# Sheet_1_2024-11-25.net
KiCad netlist of a schematic drawn in Altium Designer
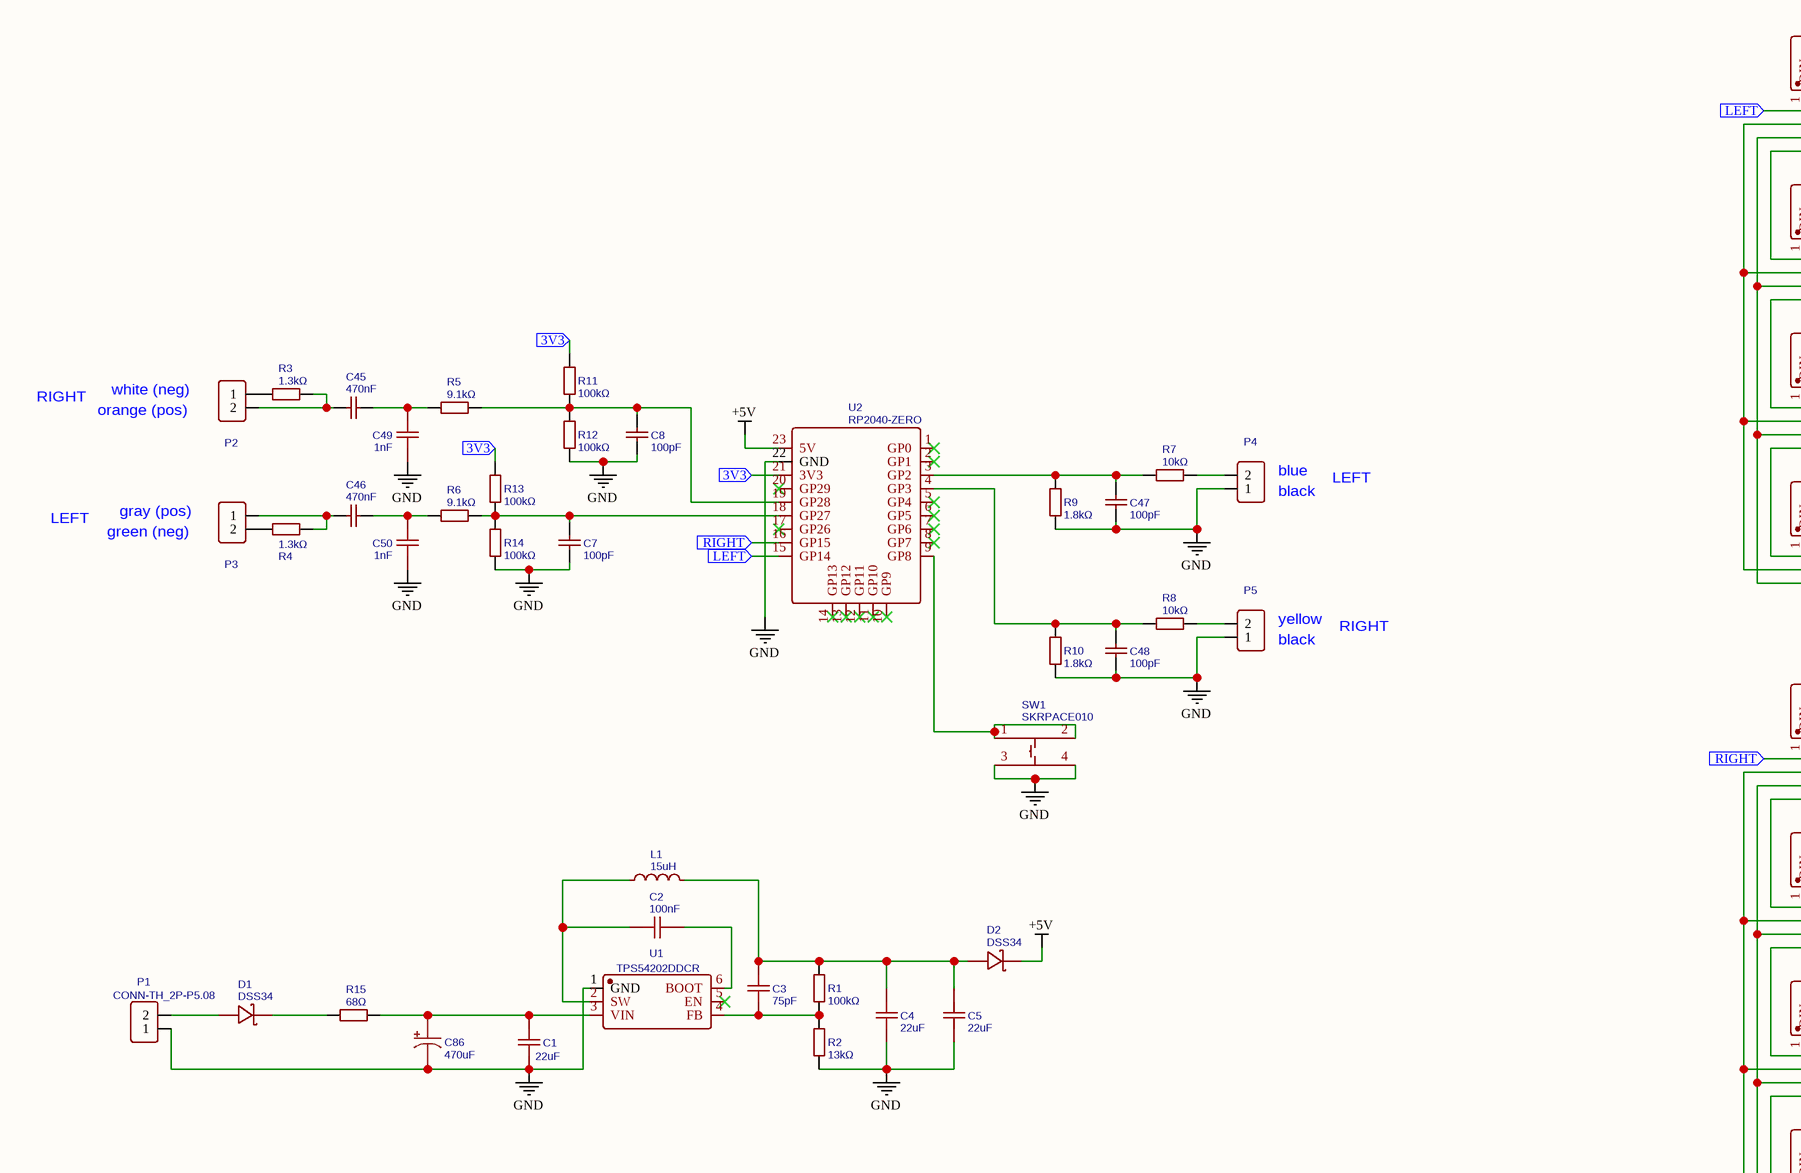
[diagram p0: Sheet_1_2024-11-25.schdoc, left]
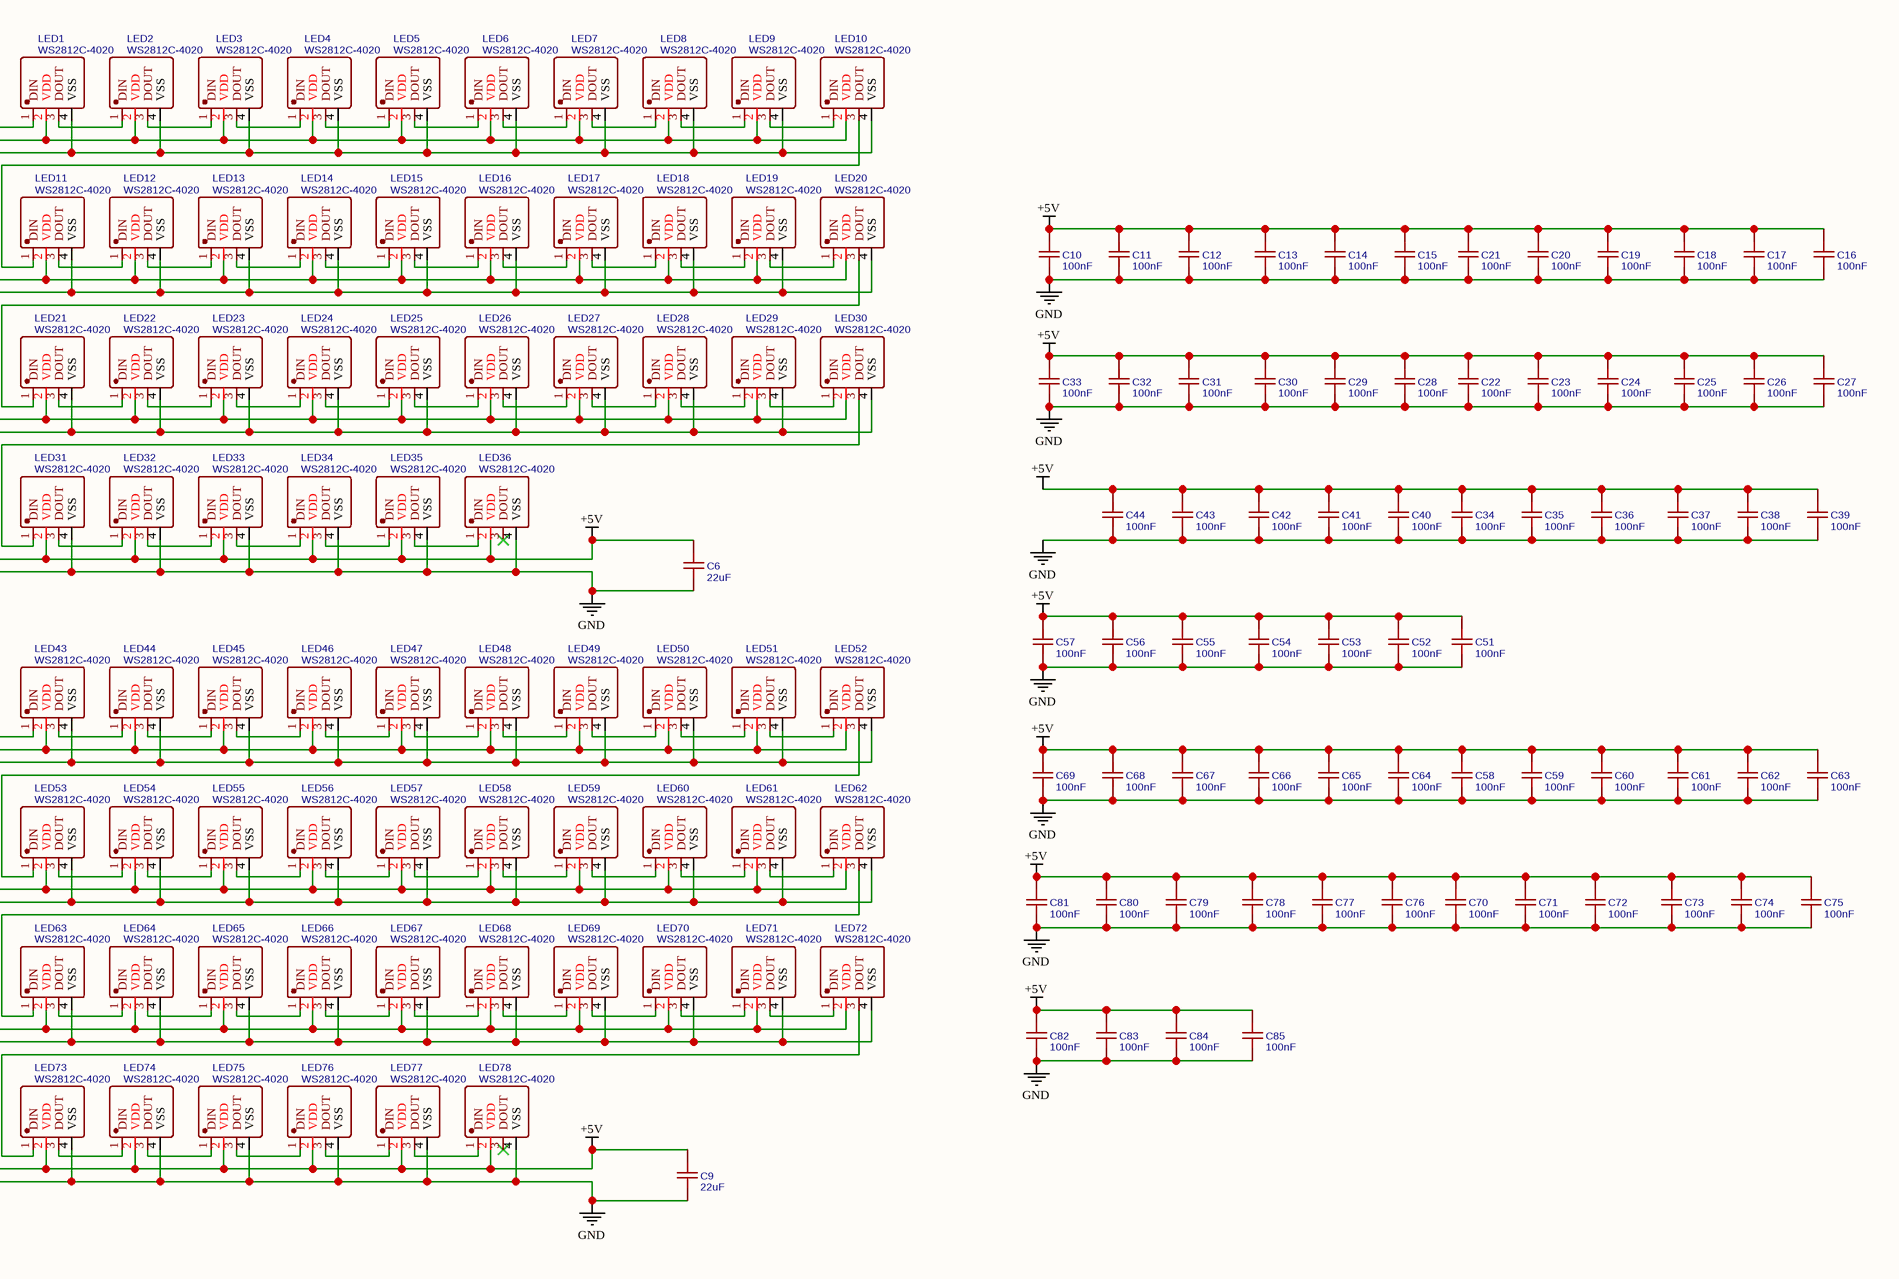
[diagram p1: Sheet_1_2024-11-25.schdoc, right]

(export (version "E")
  (design (tool "Eeschema 10.0.6"))
  (components
    (comp (ref "C1")
      (value "22uF")
      (fields
        (field (name "MANUFACTURER") "Samsung Electro-Mechanics")
        (field (name "MANUFACTURER PART") "CL21A226MAYNNNE")
        (field (name "CONTRIBUTOR") "LCSC")
      )
      (libsource (lib "altium-import") (part "root_1_22uF_"))
    )
    (comp (ref "C2")
      (value "100nF")
      (fields
        (field (name "MANUFACTURER PART") "CL05B104KO5NNNC")
        (field (name "MANUFACTURER") "SAMSUNG(三星)")
      )
      (libsource (lib "altium-import") (part "root_2_100nF_"))
    )
    (comp (ref "C3")
      (value "75pF")
      (fields
        (field (name "MANUFACTURER") "YAGEO(国巨)")
        (field (name "MANUFACTURER PART") "CC0603JRNPO9BN750")
        (field (name "CONTRIBUTOR") "LCSC")
      )
      (libsource (lib "altium-import") (part "root_0_75pF_"))
    )
    (comp (ref "C4")
      (value "22uF")
      (fields (field (name "MANUFACTURER") "SAMSUNG") (field (name "MANUFACTURER PART") "CL10A226MQ8NRNC"))
      (libsource (lib "altium-import") (part "root_1_22uF_"))
    )
    (comp (ref "C5")
      (value "22uF")
      (fields (field (name "MANUFACTURER") "SAMSUNG") (field (name "MANUFACTURER PART") "CL10A226MQ8NRNC"))
      (libsource (lib "altium-import") (part "root_1_22uF_"))
    )
    (comp (ref "C6")
      (value "22uF")
      (fields (field (name "MANUFACTURER") "SAMSUNG") (field (name "MANUFACTURER PART") "CL10A226MQ8NRNC"))
      (libsource (lib "altium-import") (part "root_1_22uF_"))
    )
    (comp (ref "C7")
      (value "100pF")
      (fields
        (field (name "MANUFACTURER PART") "CL10C101JB8NNNC")
        (field (name "MANUFACTURER") "SAMSUNG(三星)")
      )
      (libsource (lib "altium-import") (part "root_1_100pF_"))
    )
    (comp (ref "C8")
      (value "100pF")
      (fields
        (field (name "MANUFACTURER PART") "CL10C101JB8NNNC")
        (field (name "MANUFACTURER") "SAMSUNG(三星)")
      )
      (libsource (lib "altium-import") (part "root_1_100pF_"))
    )
    (comp (ref "C9")
      (value "22uF")
      (fields (field (name "MANUFACTURER") "SAMSUNG") (field (name "MANUFACTURER PART") "CL10A226MQ8NRNC"))
      (libsource (lib "altium-import") (part "root_1_22uF_"))
    )
    (comp (ref "C10")
      (value "100nF")
      (fields
        (field (name "MANUFACTURER PART") "CL05B104KO5NNNC")
        (field (name "MANUFACTURER") "SAMSUNG(三星)")
      )
      (libsource (lib "altium-import") (part "root_1_100nF_"))
    )
    (comp (ref "C11")
      (value "100nF")
      (fields
        (field (name "MANUFACTURER PART") "CL05B104KO5NNNC")
        (field (name "MANUFACTURER") "SAMSUNG(三星)")
      )
      (libsource (lib "altium-import") (part "root_1_100nF_"))
    )
    (comp (ref "C12")
      (value "100nF")
      (fields
        (field (name "MANUFACTURER PART") "CL05B104KO5NNNC")
        (field (name "MANUFACTURER") "SAMSUNG(三星)")
      )
      (libsource (lib "altium-import") (part "root_1_100nF_"))
    )
    (comp (ref "C13")
      (value "100nF")
      (fields
        (field (name "MANUFACTURER PART") "CL05B104KO5NNNC")
        (field (name "MANUFACTURER") "SAMSUNG(三星)")
      )
      (libsource (lib "altium-import") (part "root_1_100nF_"))
    )
    (comp (ref "C14")
      (value "100nF")
      (fields
        (field (name "MANUFACTURER PART") "CL05B104KO5NNNC")
        (field (name "MANUFACTURER") "SAMSUNG(三星)")
      )
      (libsource (lib "altium-import") (part "root_1_100nF_"))
    )
    (comp (ref "C15")
      (value "100nF")
      (fields
        (field (name "MANUFACTURER PART") "CL05B104KO5NNNC")
        (field (name "MANUFACTURER") "SAMSUNG(三星)")
      )
      (libsource (lib "altium-import") (part "root_1_100nF_"))
    )
    (comp (ref "C16")
      (value "100nF")
      (fields
        (field (name "MANUFACTURER PART") "CL05B104KO5NNNC")
        (field (name "MANUFACTURER") "SAMSUNG(三星)")
      )
      (libsource (lib "altium-import") (part "root_1_100nF_"))
    )
    (comp (ref "C17")
      (value "100nF")
      (fields
        (field (name "MANUFACTURER PART") "CL05B104KO5NNNC")
        (field (name "MANUFACTURER") "SAMSUNG(三星)")
      )
      (libsource (lib "altium-import") (part "root_1_100nF_"))
    )
    (comp (ref "C18")
      (value "100nF")
      (fields
        (field (name "MANUFACTURER PART") "CL05B104KO5NNNC")
        (field (name "MANUFACTURER") "SAMSUNG(三星)")
      )
      (libsource (lib "altium-import") (part "root_1_100nF_"))
    )
    (comp (ref "C19")
      (value "100nF")
      (fields
        (field (name "MANUFACTURER PART") "CL05B104KO5NNNC")
        (field (name "MANUFACTURER") "SAMSUNG(三星)")
      )
      (libsource (lib "altium-import") (part "root_1_100nF_"))
    )
    (comp (ref "C20")
      (value "100nF")
      (fields
        (field (name "MANUFACTURER PART") "CL05B104KO5NNNC")
        (field (name "MANUFACTURER") "SAMSUNG(三星)")
      )
      (libsource (lib "altium-import") (part "root_1_100nF_"))
    )
    (comp (ref "C21")
      (value "100nF")
      (fields
        (field (name "MANUFACTURER PART") "CL05B104KO5NNNC")
        (field (name "MANUFACTURER") "SAMSUNG(三星)")
      )
      (libsource (lib "altium-import") (part "root_1_100nF_"))
    )
    (comp (ref "C22")
      (value "100nF")
      (fields
        (field (name "MANUFACTURER PART") "CL05B104KO5NNNC")
        (field (name "MANUFACTURER") "SAMSUNG(三星)")
      )
      (libsource (lib "altium-import") (part "root_1_100nF_"))
    )
    (comp (ref "C23")
      (value "100nF")
      (fields
        (field (name "MANUFACTURER PART") "CL05B104KO5NNNC")
        (field (name "MANUFACTURER") "SAMSUNG(三星)")
      )
      (libsource (lib "altium-import") (part "root_1_100nF_"))
    )
    (comp (ref "C24")
      (value "100nF")
      (fields
        (field (name "MANUFACTURER PART") "CL05B104KO5NNNC")
        (field (name "MANUFACTURER") "SAMSUNG(三星)")
      )
      (libsource (lib "altium-import") (part "root_1_100nF_"))
    )
    (comp (ref "C25")
      (value "100nF")
      (fields
        (field (name "MANUFACTURER PART") "CL05B104KO5NNNC")
        (field (name "MANUFACTURER") "SAMSUNG(三星)")
      )
      (libsource (lib "altium-import") (part "root_1_100nF_"))
    )
    (comp (ref "C26")
      (value "100nF")
      (fields
        (field (name "MANUFACTURER PART") "CL05B104KO5NNNC")
        (field (name "MANUFACTURER") "SAMSUNG(三星)")
      )
      (libsource (lib "altium-import") (part "root_1_100nF_"))
    )
    (comp (ref "C27")
      (value "100nF")
      (fields
        (field (name "MANUFACTURER PART") "CL05B104KO5NNNC")
        (field (name "MANUFACTURER") "SAMSUNG(三星)")
      )
      (libsource (lib "altium-import") (part "root_1_100nF_"))
    )
    (comp (ref "C28")
      (value "100nF")
      (fields
        (field (name "MANUFACTURER PART") "CL05B104KO5NNNC")
        (field (name "MANUFACTURER") "SAMSUNG(三星)")
      )
      (libsource (lib "altium-import") (part "root_1_100nF_"))
    )
    (comp (ref "C29")
      (value "100nF")
      (fields
        (field (name "MANUFACTURER PART") "CL05B104KO5NNNC")
        (field (name "MANUFACTURER") "SAMSUNG(三星)")
      )
      (libsource (lib "altium-import") (part "root_1_100nF_"))
    )
    (comp (ref "C30")
      (value "100nF")
      (fields
        (field (name "MANUFACTURER PART") "CL05B104KO5NNNC")
        (field (name "MANUFACTURER") "SAMSUNG(三星)")
      )
      (libsource (lib "altium-import") (part "root_1_100nF_"))
    )
    (comp (ref "C31")
      (value "100nF")
      (fields
        (field (name "MANUFACTURER PART") "CL05B104KO5NNNC")
        (field (name "MANUFACTURER") "SAMSUNG(三星)")
      )
      (libsource (lib "altium-import") (part "root_1_100nF_"))
    )
    (comp (ref "C32")
      (value "100nF")
      (fields
        (field (name "MANUFACTURER PART") "CL05B104KO5NNNC")
        (field (name "MANUFACTURER") "SAMSUNG(三星)")
      )
      (libsource (lib "altium-import") (part "root_1_100nF_"))
    )
    (comp (ref "C33")
      (value "100nF")
      (fields
        (field (name "MANUFACTURER PART") "CL05B104KO5NNNC")
        (field (name "MANUFACTURER") "SAMSUNG(三星)")
      )
      (libsource (lib "altium-import") (part "root_1_100nF_"))
    )
    (comp (ref "C34")
      (value "100nF")
      (fields
        (field (name "MANUFACTURER PART") "CL05B104KO5NNNC")
        (field (name "MANUFACTURER") "SAMSUNG(三星)")
      )
      (libsource (lib "altium-import") (part "root_1_100nF_"))
    )
    (comp (ref "C35")
      (value "100nF")
      (fields
        (field (name "MANUFACTURER PART") "CL05B104KO5NNNC")
        (field (name "MANUFACTURER") "SAMSUNG(三星)")
      )
      (libsource (lib "altium-import") (part "root_1_100nF_"))
    )
    (comp (ref "C36")
      (value "100nF")
      (fields
        (field (name "MANUFACTURER PART") "CL05B104KO5NNNC")
        (field (name "MANUFACTURER") "SAMSUNG(三星)")
      )
      (libsource (lib "altium-import") (part "root_1_100nF_"))
    )
    (comp (ref "C37")
      (value "100nF")
      (fields
        (field (name "MANUFACTURER PART") "CL05B104KO5NNNC")
        (field (name "MANUFACTURER") "SAMSUNG(三星)")
      )
      (libsource (lib "altium-import") (part "root_1_100nF_"))
    )
    (comp (ref "C38")
      (value "100nF")
      (fields
        (field (name "MANUFACTURER PART") "CL05B104KO5NNNC")
        (field (name "MANUFACTURER") "SAMSUNG(三星)")
      )
      (libsource (lib "altium-import") (part "root_1_100nF_"))
    )
    (comp (ref "C39")
      (value "100nF")
      (fields
        (field (name "MANUFACTURER PART") "CL05B104KO5NNNC")
        (field (name "MANUFACTURER") "SAMSUNG(三星)")
      )
      (libsource (lib "altium-import") (part "root_1_100nF_"))
    )
    (comp (ref "C40")
      (value "100nF")
      (fields
        (field (name "MANUFACTURER PART") "CL05B104KO5NNNC")
        (field (name "MANUFACTURER") "SAMSUNG(三星)")
      )
      (libsource (lib "altium-import") (part "root_1_100nF_"))
    )
    (comp (ref "C41")
      (value "100nF")
      (fields
        (field (name "MANUFACTURER PART") "CL05B104KO5NNNC")
        (field (name "MANUFACTURER") "SAMSUNG(三星)")
      )
      (libsource (lib "altium-import") (part "root_1_100nF_"))
    )
    (comp (ref "C42")
      (value "100nF")
      (fields
        (field (name "MANUFACTURER PART") "CL05B104KO5NNNC")
        (field (name "MANUFACTURER") "SAMSUNG(三星)")
      )
      (libsource (lib "altium-import") (part "root_1_100nF_"))
    )
    (comp (ref "C43")
      (value "100nF")
      (fields
        (field (name "MANUFACTURER PART") "CL05B104KO5NNNC")
        (field (name "MANUFACTURER") "SAMSUNG(三星)")
      )
      (libsource (lib "altium-import") (part "root_1_100nF_"))
    )
    (comp (ref "C44")
      (value "100nF")
      (fields
        (field (name "MANUFACTURER PART") "CL05B104KO5NNNC")
        (field (name "MANUFACTURER") "SAMSUNG(三星)")
      )
      (libsource (lib "altium-import") (part "root_1_100nF_"))
    )
    (comp (ref "C45")
      (value "470nF")
      (fields
        (field (name "MANUFACTURER PART") "CL21B474KBFNNNE")
        (field (name "MANUFACTURER") "SAMSUNG(三星)")
      )
      (libsource (lib "altium-import") (part "root_0_470nF_"))
    )
    (comp (ref "C46")
      (value "470nF")
      (fields
        (field (name "MANUFACTURER PART") "CL21B474KBFNNNE")
        (field (name "MANUFACTURER") "SAMSUNG(三星)")
      )
      (libsource (lib "altium-import") (part "root_0_470nF_"))
    )
    (comp (ref "C47")
      (value "100pF")
      (fields
        (field (name "MANUFACTURER PART") "CL10C101JB8NNNC")
        (field (name "MANUFACTURER") "SAMSUNG(三星)")
      )
      (libsource (lib "altium-import") (part "root_1_100pF_"))
    )
    (comp (ref "C48")
      (value "100pF")
      (fields
        (field (name "MANUFACTURER PART") "CL10C101JB8NNNC")
        (field (name "MANUFACTURER") "SAMSUNG(三星)")
      )
      (libsource (lib "altium-import") (part "root_1_100pF_"))
    )
    (comp (ref "C49")
      (value "1nF")
      (fields
        (field (name "MANUFACTURER") "SAMSUNG(三星)")
        (field (name "MANUFACTURER PART") "CL10C102JB8NNNC")
        (field (name "CONTRIBUTOR") "LCSC")
      )
      (libsource (lib "altium-import") (part "root_1_1nF_"))
    )
    (comp (ref "C50")
      (value "1nF")
      (fields
        (field (name "MANUFACTURER") "SAMSUNG(三星)")
        (field (name "MANUFACTURER PART") "CL10C102JB8NNNC")
        (field (name "CONTRIBUTOR") "LCSC")
      )
      (libsource (lib "altium-import") (part "root_1_1nF_"))
    )
    (comp (ref "C51")
      (value "100nF")
      (fields
        (field (name "MANUFACTURER PART") "CL05B104KO5NNNC")
        (field (name "MANUFACTURER") "SAMSUNG(三星)")
      )
      (libsource (lib "altium-import") (part "root_1_100nF_"))
    )
    (comp (ref "C52")
      (value "100nF")
      (fields
        (field (name "MANUFACTURER PART") "CL05B104KO5NNNC")
        (field (name "MANUFACTURER") "SAMSUNG(三星)")
      )
      (libsource (lib "altium-import") (part "root_1_100nF_"))
    )
    (comp (ref "C53")
      (value "100nF")
      (fields
        (field (name "MANUFACTURER PART") "CL05B104KO5NNNC")
        (field (name "MANUFACTURER") "SAMSUNG(三星)")
      )
      (libsource (lib "altium-import") (part "root_1_100nF_"))
    )
    (comp (ref "C54")
      (value "100nF")
      (fields
        (field (name "MANUFACTURER PART") "CL05B104KO5NNNC")
        (field (name "MANUFACTURER") "SAMSUNG(三星)")
      )
      (libsource (lib "altium-import") (part "root_1_100nF_"))
    )
    (comp (ref "C55")
      (value "100nF")
      (fields
        (field (name "MANUFACTURER PART") "CL05B104KO5NNNC")
        (field (name "MANUFACTURER") "SAMSUNG(三星)")
      )
      (libsource (lib "altium-import") (part "root_1_100nF_"))
    )
    (comp (ref "C56")
      (value "100nF")
      (fields
        (field (name "MANUFACTURER PART") "CL05B104KO5NNNC")
        (field (name "MANUFACTURER") "SAMSUNG(三星)")
      )
      (libsource (lib "altium-import") (part "root_1_100nF_"))
    )
    (comp (ref "C57")
      (value "100nF")
      (fields
        (field (name "MANUFACTURER PART") "CL05B104KO5NNNC")
        (field (name "MANUFACTURER") "SAMSUNG(三星)")
      )
      (libsource (lib "altium-import") (part "root_1_100nF_"))
    )
    (comp (ref "C58")
      (value "100nF")
      (fields
        (field (name "MANUFACTURER PART") "CL05B104KO5NNNC")
        (field (name "MANUFACTURER") "SAMSUNG(三星)")
      )
      (libsource (lib "altium-import") (part "root_1_100nF_"))
    )
    (comp (ref "C59")
      (value "100nF")
      (fields
        (field (name "MANUFACTURER PART") "CL05B104KO5NNNC")
        (field (name "MANUFACTURER") "SAMSUNG(三星)")
      )
      (libsource (lib "altium-import") (part "root_1_100nF_"))
    )
    (comp (ref "C60")
      (value "100nF")
      (fields
        (field (name "MANUFACTURER PART") "CL05B104KO5NNNC")
        (field (name "MANUFACTURER") "SAMSUNG(三星)")
      )
      (libsource (lib "altium-import") (part "root_1_100nF_"))
    )
    (comp (ref "C61")
      (value "100nF")
      (fields
        (field (name "MANUFACTURER PART") "CL05B104KO5NNNC")
        (field (name "MANUFACTURER") "SAMSUNG(三星)")
      )
      (libsource (lib "altium-import") (part "root_1_100nF_"))
    )
    (comp (ref "C62")
      (value "100nF")
      (fields
        (field (name "MANUFACTURER PART") "CL05B104KO5NNNC")
        (field (name "MANUFACTURER") "SAMSUNG(三星)")
      )
      (libsource (lib "altium-import") (part "root_1_100nF_"))
    )
    (comp (ref "C63")
      (value "100nF")
      (fields
        (field (name "MANUFACTURER PART") "CL05B104KO5NNNC")
        (field (name "MANUFACTURER") "SAMSUNG(三星)")
      )
      (libsource (lib "altium-import") (part "root_1_100nF_"))
    )
    (comp (ref "C64")
      (value "100nF")
      (fields
        (field (name "MANUFACTURER PART") "CL05B104KO5NNNC")
        (field (name "MANUFACTURER") "SAMSUNG(三星)")
      )
      (libsource (lib "altium-import") (part "root_1_100nF_"))
    )
    (comp (ref "C65")
      (value "100nF")
      (fields
        (field (name "MANUFACTURER PART") "CL05B104KO5NNNC")
        (field (name "MANUFACTURER") "SAMSUNG(三星)")
      )
      (libsource (lib "altium-import") (part "root_1_100nF_"))
    )
    (comp (ref "C66")
      (value "100nF")
      (fields
        (field (name "MANUFACTURER PART") "CL05B104KO5NNNC")
        (field (name "MANUFACTURER") "SAMSUNG(三星)")
      )
      (libsource (lib "altium-import") (part "root_1_100nF_"))
    )
    (comp (ref "C67")
      (value "100nF")
      (fields
        (field (name "MANUFACTURER PART") "CL05B104KO5NNNC")
        (field (name "MANUFACTURER") "SAMSUNG(三星)")
      )
      (libsource (lib "altium-import") (part "root_1_100nF_"))
    )
    (comp (ref "C68")
      (value "100nF")
      (fields
        (field (name "MANUFACTURER PART") "CL05B104KO5NNNC")
        (field (name "MANUFACTURER") "SAMSUNG(三星)")
      )
      (libsource (lib "altium-import") (part "root_1_100nF_"))
    )
    (comp (ref "C69")
      (value "100nF")
      (fields
        (field (name "MANUFACTURER PART") "CL05B104KO5NNNC")
        (field (name "MANUFACTURER") "SAMSUNG(三星)")
      )
      (libsource (lib "altium-import") (part "root_1_100nF_"))
    )
    (comp (ref "C70")
      (value "100nF")
      (fields
        (field (name "MANUFACTURER PART") "CL05B104KO5NNNC")
        (field (name "MANUFACTURER") "SAMSUNG(三星)")
      )
      (libsource (lib "altium-import") (part "root_1_100nF_"))
    )
    (comp (ref "C71")
      (value "100nF")
      (fields
        (field (name "MANUFACTURER PART") "CL05B104KO5NNNC")
        (field (name "MANUFACTURER") "SAMSUNG(三星)")
      )
      (libsource (lib "altium-import") (part "root_1_100nF_"))
    )
    (comp (ref "C72")
      (value "100nF")
      (fields
        (field (name "MANUFACTURER PART") "CL05B104KO5NNNC")
        (field (name "MANUFACTURER") "SAMSUNG(三星)")
      )
      (libsource (lib "altium-import") (part "root_1_100nF_"))
    )
    (comp (ref "C73")
      (value "100nF")
      (fields
        (field (name "MANUFACTURER PART") "CL05B104KO5NNNC")
        (field (name "MANUFACTURER") "SAMSUNG(三星)")
      )
      (libsource (lib "altium-import") (part "root_1_100nF_"))
    )
    (comp (ref "C74")
      (value "100nF")
      (fields
        (field (name "MANUFACTURER PART") "CL05B104KO5NNNC")
        (field (name "MANUFACTURER") "SAMSUNG(三星)")
      )
      (libsource (lib "altium-import") (part "root_1_100nF_"))
    )
    (comp (ref "C75")
      (value "100nF")
      (fields
        (field (name "MANUFACTURER PART") "CL05B104KO5NNNC")
        (field (name "MANUFACTURER") "SAMSUNG(三星)")
      )
      (libsource (lib "altium-import") (part "root_1_100nF_"))
    )
    (comp (ref "C76")
      (value "100nF")
      (fields
        (field (name "MANUFACTURER PART") "CL05B104KO5NNNC")
        (field (name "MANUFACTURER") "SAMSUNG(三星)")
      )
      (libsource (lib "altium-import") (part "root_1_100nF_"))
    )
    (comp (ref "C77")
      (value "100nF")
      (fields
        (field (name "MANUFACTURER PART") "CL05B104KO5NNNC")
        (field (name "MANUFACTURER") "SAMSUNG(三星)")
      )
      (libsource (lib "altium-import") (part "root_1_100nF_"))
    )
    (comp (ref "C78")
      (value "100nF")
      (fields
        (field (name "MANUFACTURER PART") "CL05B104KO5NNNC")
        (field (name "MANUFACTURER") "SAMSUNG(三星)")
      )
      (libsource (lib "altium-import") (part "root_1_100nF_"))
    )
    (comp (ref "C79")
      (value "100nF")
      (fields
        (field (name "MANUFACTURER PART") "CL05B104KO5NNNC")
        (field (name "MANUFACTURER") "SAMSUNG(三星)")
      )
      (libsource (lib "altium-import") (part "root_1_100nF_"))
    )
    (comp (ref "C80")
      (value "100nF")
      (fields
        (field (name "MANUFACTURER PART") "CL05B104KO5NNNC")
        (field (name "MANUFACTURER") "SAMSUNG(三星)")
      )
      (libsource (lib "altium-import") (part "root_1_100nF_"))
    )
    (comp (ref "C81")
      (value "100nF")
      (fields
        (field (name "MANUFACTURER PART") "CL05B104KO5NNNC")
        (field (name "MANUFACTURER") "SAMSUNG(三星)")
      )
      (libsource (lib "altium-import") (part "root_1_100nF_"))
    )
    (comp (ref "C82")
      (value "100nF")
      (fields
        (field (name "MANUFACTURER PART") "CL05B104KO5NNNC")
        (field (name "MANUFACTURER") "SAMSUNG(三星)")
      )
      (libsource (lib "altium-import") (part "root_1_100nF_"))
    )
    (comp (ref "C83")
      (value "100nF")
      (fields
        (field (name "MANUFACTURER PART") "CL05B104KO5NNNC")
        (field (name "MANUFACTURER") "SAMSUNG(三星)")
      )
      (libsource (lib "altium-import") (part "root_1_100nF_"))
    )
    (comp (ref "C84")
      (value "100nF")
      (fields
        (field (name "MANUFACTURER PART") "CL05B104KO5NNNC")
        (field (name "MANUFACTURER") "SAMSUNG(三星)")
      )
      (libsource (lib "altium-import") (part "root_1_100nF_"))
    )
    (comp (ref "C85")
      (value "100nF")
      (fields
        (field (name "MANUFACTURER PART") "CL05B104KO5NNNC")
        (field (name "MANUFACTURER") "SAMSUNG(三星)")
      )
      (libsource (lib "altium-import") (part "root_1_100nF_"))
    )
    (comp (ref "C86")
      (value "470uF")
      (fields
        (field (name "MANUFACTURER") "ROQANG(容强)")
        (field (name "MANUFACTURER PART") "RVT1A471M0607")
        (field (name "CONTRIBUTOR") "LCSC")
      )
      (libsource (lib "altium-import") (part "root_0_470uF_"))
    )
    (comp (ref "D1")
      (value "DSS34")
      (fields (field (name "MANUFACTURER") "STARSEA"))
      (libsource (lib "altium-import") (part "root_2_DSS34_"))
    )
    (comp (ref "D2")
      (value "DSS34")
      (fields (field (name "MANUFACTURER") "STARSEA"))
      (libsource (lib "altium-import") (part "root_2_DSS34_"))
    )
    (comp (ref "L1")
      (value "15uH")
      (fields
        (field (name "MANUFACTURER") "Sunltech(韩国顺磁)")
        (field (name "MANUFACTURER PART") "SLP6028S150MTT")
        (field (name "CONTRIBUTOR") "LCSC")
      )
      (libsource (lib "altium-import") (part "root_0_15uH_"))
    )
    (comp (ref "LED1")
      (value "WS2812C-4020")
      (fields (field (name "MANUFACTURER") "worldsemi") (field (name "CONTRIBUTOR") "lcsc"))
      (libsource (lib "altium-import") (part "root_1_WS2812C-4020_"))
    )
    (comp (ref "LED2")
      (value "WS2812C-4020")
      (fields (field (name "MANUFACTURER") "worldsemi") (field (name "CONTRIBUTOR") "lcsc"))
      (libsource (lib "altium-import") (part "root_1_WS2812C-4020_"))
    )
    (comp (ref "LED3")
      (value "WS2812C-4020")
      (fields (field (name "MANUFACTURER") "worldsemi") (field (name "CONTRIBUTOR") "lcsc"))
      (libsource (lib "altium-import") (part "root_1_WS2812C-4020_"))
    )
    (comp (ref "LED4")
      (value "WS2812C-4020")
      (fields (field (name "MANUFACTURER") "worldsemi") (field (name "CONTRIBUTOR") "lcsc"))
      (libsource (lib "altium-import") (part "root_1_WS2812C-4020_"))
    )
    (comp (ref "LED5")
      (value "WS2812C-4020")
      (fields (field (name "MANUFACTURER") "worldsemi") (field (name "CONTRIBUTOR") "lcsc"))
      (libsource (lib "altium-import") (part "root_1_WS2812C-4020_"))
    )
    (comp (ref "LED6")
      (value "WS2812C-4020")
      (fields (field (name "MANUFACTURER") "worldsemi") (field (name "CONTRIBUTOR") "lcsc"))
      (libsource (lib "altium-import") (part "root_1_WS2812C-4020_"))
    )
    (comp (ref "LED7")
      (value "WS2812C-4020")
      (fields (field (name "MANUFACTURER") "worldsemi") (field (name "CONTRIBUTOR") "lcsc"))
      (libsource (lib "altium-import") (part "root_1_WS2812C-4020_"))
    )
    (comp (ref "LED8")
      (value "WS2812C-4020")
      (fields (field (name "MANUFACTURER") "worldsemi") (field (name "CONTRIBUTOR") "lcsc"))
      (libsource (lib "altium-import") (part "root_1_WS2812C-4020_"))
    )
    (comp (ref "LED9")
      (value "WS2812C-4020")
      (fields (field (name "MANUFACTURER") "worldsemi") (field (name "CONTRIBUTOR") "lcsc"))
      (libsource (lib "altium-import") (part "root_1_WS2812C-4020_"))
    )
    (comp (ref "LED10")
      (value "WS2812C-4020")
      (fields (field (name "MANUFACTURER") "worldsemi") (field (name "CONTRIBUTOR") "lcsc"))
      (libsource (lib "altium-import") (part "root_1_WS2812C-4020_"))
    )
    (comp (ref "LED11")
      (value "WS2812C-4020")
      (fields (field (name "MANUFACTURER") "worldsemi") (field (name "CONTRIBUTOR") "lcsc"))
      (libsource (lib "altium-import") (part "root_1_WS2812C-4020_"))
    )
    (comp (ref "LED12")
      (value "WS2812C-4020")
      (fields (field (name "MANUFACTURER") "worldsemi") (field (name "CONTRIBUTOR") "lcsc"))
      (libsource (lib "altium-import") (part "root_1_WS2812C-4020_"))
    )
    (comp (ref "LED13")
      (value "WS2812C-4020")
      (fields (field (name "MANUFACTURER") "worldsemi") (field (name "CONTRIBUTOR") "lcsc"))
      (libsource (lib "altium-import") (part "root_1_WS2812C-4020_"))
    )
    (comp (ref "LED14")
      (value "WS2812C-4020")
      (fields (field (name "MANUFACTURER") "worldsemi") (field (name "CONTRIBUTOR") "lcsc"))
      (libsource (lib "altium-import") (part "root_1_WS2812C-4020_"))
    )
    (comp (ref "LED15")
      (value "WS2812C-4020")
      (fields (field (name "MANUFACTURER") "worldsemi") (field (name "CONTRIBUTOR") "lcsc"))
      (libsource (lib "altium-import") (part "root_1_WS2812C-4020_"))
    )
    (comp (ref "LED16")
      (value "WS2812C-4020")
      (fields (field (name "MANUFACTURER") "worldsemi") (field (name "CONTRIBUTOR") "lcsc"))
      (libsource (lib "altium-import") (part "root_1_WS2812C-4020_"))
    )
    (comp (ref "LED17")
      (value "WS2812C-4020")
      (fields (field (name "MANUFACTURER") "worldsemi") (field (name "CONTRIBUTOR") "lcsc"))
      (libsource (lib "altium-import") (part "root_1_WS2812C-4020_"))
    )
    (comp (ref "LED18")
      (value "WS2812C-4020")
      (fields (field (name "MANUFACTURER") "worldsemi") (field (name "CONTRIBUTOR") "lcsc"))
      (libsource (lib "altium-import") (part "root_1_WS2812C-4020_"))
    )
    (comp (ref "LED19")
      (value "WS2812C-4020")
      (fields (field (name "MANUFACTURER") "worldsemi") (field (name "CONTRIBUTOR") "lcsc"))
      (libsource (lib "altium-import") (part "root_1_WS2812C-4020_"))
    )
    (comp (ref "LED20")
      (value "WS2812C-4020")
      (fields (field (name "MANUFACTURER") "worldsemi") (field (name "CONTRIBUTOR") "lcsc"))
      (libsource (lib "altium-import") (part "root_1_WS2812C-4020_"))
    )
    (comp (ref "LED21")
      (value "WS2812C-4020")
      (fields (field (name "MANUFACTURER") "worldsemi") (field (name "CONTRIBUTOR") "lcsc"))
      (libsource (lib "altium-import") (part "root_1_WS2812C-4020_"))
    )
    (comp (ref "LED22")
      (value "WS2812C-4020")
      (fields (field (name "MANUFACTURER") "worldsemi") (field (name "CONTRIBUTOR") "lcsc"))
      (libsource (lib "altium-import") (part "root_1_WS2812C-4020_"))
    )
    (comp (ref "LED23")
      (value "WS2812C-4020")
      (fields (field (name "MANUFACTURER") "worldsemi") (field (name "CONTRIBUTOR") "lcsc"))
      (libsource (lib "altium-import") (part "root_1_WS2812C-4020_"))
    )
    (comp (ref "LED24")
      (value "WS2812C-4020")
      (fields (field (name "MANUFACTURER") "worldsemi") (field (name "CONTRIBUTOR") "lcsc"))
      (libsource (lib "altium-import") (part "root_1_WS2812C-4020_"))
    )
    (comp (ref "LED25")
      (value "WS2812C-4020")
      (fields (field (name "MANUFACTURER") "worldsemi") (field (name "CONTRIBUTOR") "lcsc"))
      (libsource (lib "altium-import") (part "root_1_WS2812C-4020_"))
    )
    (comp (ref "LED26")
      (value "WS2812C-4020")
      (fields (field (name "MANUFACTURER") "worldsemi") (field (name "CONTRIBUTOR") "lcsc"))
      (libsource (lib "altium-import") (part "root_1_WS2812C-4020_"))
    )
    (comp (ref "LED27")
      (value "WS2812C-4020")
      (fields (field (name "MANUFACTURER") "worldsemi") (field (name "CONTRIBUTOR") "lcsc"))
      (libsource (lib "altium-import") (part "root_1_WS2812C-4020_"))
    )
    (comp (ref "LED28")
      (value "WS2812C-4020")
      (fields (field (name "MANUFACTURER") "worldsemi") (field (name "CONTRIBUTOR") "lcsc"))
      (libsource (lib "altium-import") (part "root_1_WS2812C-4020_"))
    )
    (comp (ref "LED29")
      (value "WS2812C-4020")
      (fields (field (name "MANUFACTURER") "worldsemi") (field (name "CONTRIBUTOR") "lcsc"))
      (libsource (lib "altium-import") (part "root_1_WS2812C-4020_"))
    )
    (comp (ref "LED30")
      (value "WS2812C-4020")
      (fields (field (name "MANUFACTURER") "worldsemi") (field (name "CONTRIBUTOR") "lcsc"))
      (libsource (lib "altium-import") (part "root_1_WS2812C-4020_"))
    )
    (comp (ref "LED31")
      (value "WS2812C-4020")
      (fields (field (name "MANUFACTURER") "worldsemi") (field (name "CONTRIBUTOR") "lcsc"))
      (libsource (lib "altium-import") (part "root_1_WS2812C-4020_"))
    )
    (comp (ref "LED32")
      (value "WS2812C-4020")
      (fields (field (name "MANUFACTURER") "worldsemi") (field (name "CONTRIBUTOR") "lcsc"))
      (libsource (lib "altium-import") (part "root_1_WS2812C-4020_"))
    )
    (comp (ref "LED33")
      (value "WS2812C-4020")
      (fields (field (name "MANUFACTURER") "worldsemi") (field (name "CONTRIBUTOR") "lcsc"))
      (libsource (lib "altium-import") (part "root_1_WS2812C-4020_"))
    )
    (comp (ref "LED34")
      (value "WS2812C-4020")
      (fields (field (name "MANUFACTURER") "worldsemi") (field (name "CONTRIBUTOR") "lcsc"))
      (libsource (lib "altium-import") (part "root_1_WS2812C-4020_"))
    )
    (comp (ref "LED35")
      (value "WS2812C-4020")
      (fields (field (name "MANUFACTURER") "worldsemi") (field (name "CONTRIBUTOR") "lcsc"))
      (libsource (lib "altium-import") (part "root_1_WS2812C-4020_"))
    )
    (comp (ref "LED36")
      (value "WS2812C-4020")
      (fields (field (name "MANUFACTURER") "worldsemi") (field (name "CONTRIBUTOR") "lcsc"))
      (libsource (lib "altium-import") (part "root_1_WS2812C-4020_"))
    )
    (comp (ref "LED43")
      (value "WS2812C-4020")
      (fields (field (name "MANUFACTURER") "worldsemi") (field (name "CONTRIBUTOR") "lcsc"))
      (libsource (lib "altium-import") (part "root_1_WS2812C-4020_"))
    )
    (comp (ref "LED44")
      (value "WS2812C-4020")
      (fields (field (name "MANUFACTURER") "worldsemi") (field (name "CONTRIBUTOR") "lcsc"))
      (libsource (lib "altium-import") (part "root_1_WS2812C-4020_"))
    )
    (comp (ref "LED45")
      (value "WS2812C-4020")
      (fields (field (name "MANUFACTURER") "worldsemi") (field (name "CONTRIBUTOR") "lcsc"))
      (libsource (lib "altium-import") (part "root_1_WS2812C-4020_"))
    )
    (comp (ref "LED46")
      (value "WS2812C-4020")
      (fields (field (name "MANUFACTURER") "worldsemi") (field (name "CONTRIBUTOR") "lcsc"))
      (libsource (lib "altium-import") (part "root_1_WS2812C-4020_"))
    )
    (comp (ref "LED47")
      (value "WS2812C-4020")
      (fields (field (name "MANUFACTURER") "worldsemi") (field (name "CONTRIBUTOR") "lcsc"))
      (libsource (lib "altium-import") (part "root_1_WS2812C-4020_"))
    )
    (comp (ref "LED48")
      (value "WS2812C-4020")
      (fields (field (name "MANUFACTURER") "worldsemi") (field (name "CONTRIBUTOR") "lcsc"))
      (libsource (lib "altium-import") (part "root_1_WS2812C-4020_"))
    )
    (comp (ref "LED49")
      (value "WS2812C-4020")
      (fields (field (name "MANUFACTURER") "worldsemi") (field (name "CONTRIBUTOR") "lcsc"))
      (libsource (lib "altium-import") (part "root_1_WS2812C-4020_"))
    )
    (comp (ref "LED50")
      (value "WS2812C-4020")
      (fields (field (name "MANUFACTURER") "worldsemi") (field (name "CONTRIBUTOR") "lcsc"))
      (libsource (lib "altium-import") (part "root_1_WS2812C-4020_"))
    )
    (comp (ref "LED51")
      (value "WS2812C-4020")
      (fields (field (name "MANUFACTURER") "worldsemi") (field (name "CONTRIBUTOR") "lcsc"))
      (libsource (lib "altium-import") (part "root_1_WS2812C-4020_"))
    )
    (comp (ref "LED52")
      (value "WS2812C-4020")
      (fields (field (name "MANUFACTURER") "worldsemi") (field (name "CONTRIBUTOR") "lcsc"))
      (libsource (lib "altium-import") (part "root_1_WS2812C-4020_"))
    )
    (comp (ref "LED53")
      (value "WS2812C-4020")
      (fields (field (name "MANUFACTURER") "worldsemi") (field (name "CONTRIBUTOR") "lcsc"))
      (libsource (lib "altium-import") (part "root_1_WS2812C-4020_"))
    )
    (comp (ref "LED54")
      (value "WS2812C-4020")
      (fields (field (name "MANUFACTURER") "worldsemi") (field (name "CONTRIBUTOR") "lcsc"))
      (libsource (lib "altium-import") (part "root_1_WS2812C-4020_"))
    )
    (comp (ref "LED55")
      (value "WS2812C-4020")
      (fields (field (name "MANUFACTURER") "worldsemi") (field (name "CONTRIBUTOR") "lcsc"))
      (libsource (lib "altium-import") (part "root_1_WS2812C-4020_"))
    )
    (comp (ref "LED56")
      (value "WS2812C-4020")
      (fields (field (name "MANUFACTURER") "worldsemi") (field (name "CONTRIBUTOR") "lcsc"))
      (libsource (lib "altium-import") (part "root_1_WS2812C-4020_"))
    )
    (comp (ref "LED57")
      (value "WS2812C-4020")
      (fields (field (name "MANUFACTURER") "worldsemi") (field (name "CONTRIBUTOR") "lcsc"))
      (libsource (lib "altium-import") (part "root_1_WS2812C-4020_"))
    )
    (comp (ref "LED58")
      (value "WS2812C-4020")
      (fields (field (name "MANUFACTURER") "worldsemi") (field (name "CONTRIBUTOR") "lcsc"))
      (libsource (lib "altium-import") (part "root_1_WS2812C-4020_"))
    )
    (comp (ref "LED59")
      (value "WS2812C-4020")
      (fields (field (name "MANUFACTURER") "worldsemi") (field (name "CONTRIBUTOR") "lcsc"))
      (libsource (lib "altium-import") (part "root_1_WS2812C-4020_"))
    )
    (comp (ref "LED60")
      (value "WS2812C-4020")
      (fields (field (name "MANUFACTURER") "worldsemi") (field (name "CONTRIBUTOR") "lcsc"))
      (libsource (lib "altium-import") (part "root_1_WS2812C-4020_"))
    )
    (comp (ref "LED61")
      (value "WS2812C-4020")
      (fields (field (name "MANUFACTURER") "worldsemi") (field (name "CONTRIBUTOR") "lcsc"))
      (libsource (lib "altium-import") (part "root_1_WS2812C-4020_"))
    )
    (comp (ref "LED62")
      (value "WS2812C-4020")
      (fields (field (name "MANUFACTURER") "worldsemi") (field (name "CONTRIBUTOR") "lcsc"))
      (libsource (lib "altium-import") (part "root_1_WS2812C-4020_"))
    )
    (comp (ref "LED63")
      (value "WS2812C-4020")
      (fields (field (name "MANUFACTURER") "worldsemi") (field (name "CONTRIBUTOR") "lcsc"))
      (libsource (lib "altium-import") (part "root_1_WS2812C-4020_"))
    )
    (comp (ref "LED64")
      (value "WS2812C-4020")
      (fields (field (name "MANUFACTURER") "worldsemi") (field (name "CONTRIBUTOR") "lcsc"))
      (libsource (lib "altium-import") (part "root_1_WS2812C-4020_"))
    )
    (comp (ref "LED65")
      (value "WS2812C-4020")
      (fields (field (name "MANUFACTURER") "worldsemi") (field (name "CONTRIBUTOR") "lcsc"))
      (libsource (lib "altium-import") (part "root_1_WS2812C-4020_"))
    )
    (comp (ref "LED66")
      (value "WS2812C-4020")
      (fields (field (name "MANUFACTURER") "worldsemi") (field (name "CONTRIBUTOR") "lcsc"))
      (libsource (lib "altium-import") (part "root_1_WS2812C-4020_"))
    )
    (comp (ref "LED67")
      (value "WS2812C-4020")
      (fields (field (name "MANUFACTURER") "worldsemi") (field (name "CONTRIBUTOR") "lcsc"))
      (libsource (lib "altium-import") (part "root_1_WS2812C-4020_"))
    )
    (comp (ref "LED68")
      (value "WS2812C-4020")
      (fields (field (name "MANUFACTURER") "worldsemi") (field (name "CONTRIBUTOR") "lcsc"))
      (libsource (lib "altium-import") (part "root_1_WS2812C-4020_"))
    )
    (comp (ref "LED69")
      (value "WS2812C-4020")
      (fields (field (name "MANUFACTURER") "worldsemi") (field (name "CONTRIBUTOR") "lcsc"))
      (libsource (lib "altium-import") (part "root_1_WS2812C-4020_"))
    )
    (comp (ref "LED70")
      (value "WS2812C-4020")
      (fields (field (name "MANUFACTURER") "worldsemi") (field (name "CONTRIBUTOR") "lcsc"))
      (libsource (lib "altium-import") (part "root_1_WS2812C-4020_"))
    )
    (comp (ref "LED71")
      (value "WS2812C-4020")
      (fields (field (name "MANUFACTURER") "worldsemi") (field (name "CONTRIBUTOR") "lcsc"))
      (libsource (lib "altium-import") (part "root_1_WS2812C-4020_"))
    )
    (comp (ref "LED72")
      (value "WS2812C-4020")
      (fields (field (name "MANUFACTURER") "worldsemi") (field (name "CONTRIBUTOR") "lcsc"))
      (libsource (lib "altium-import") (part "root_1_WS2812C-4020_"))
    )
    (comp (ref "LED73")
      (value "WS2812C-4020")
      (fields (field (name "MANUFACTURER") "worldsemi") (field (name "CONTRIBUTOR") "lcsc"))
      (libsource (lib "altium-import") (part "root_1_WS2812C-4020_"))
    )
    (comp (ref "LED74")
      (value "WS2812C-4020")
      (fields (field (name "MANUFACTURER") "worldsemi") (field (name "CONTRIBUTOR") "lcsc"))
      (libsource (lib "altium-import") (part "root_1_WS2812C-4020_"))
    )
    (comp (ref "LED75")
      (value "WS2812C-4020")
      (fields (field (name "MANUFACTURER") "worldsemi") (field (name "CONTRIBUTOR") "lcsc"))
      (libsource (lib "altium-import") (part "root_1_WS2812C-4020_"))
    )
    (comp (ref "LED76")
      (value "WS2812C-4020")
      (fields (field (name "MANUFACTURER") "worldsemi") (field (name "CONTRIBUTOR") "lcsc"))
      (libsource (lib "altium-import") (part "root_1_WS2812C-4020_"))
    )
    (comp (ref "LED77")
      (value "WS2812C-4020")
      (fields (field (name "MANUFACTURER") "worldsemi") (field (name "CONTRIBUTOR") "lcsc"))
      (libsource (lib "altium-import") (part "root_1_WS2812C-4020_"))
    )
    (comp (ref "LED78")
      (value "WS2812C-4020")
      (fields (field (name "MANUFACTURER") "worldsemi") (field (name "CONTRIBUTOR") "lcsc"))
      (libsource (lib "altium-import") (part "root_1_WS2812C-4020_"))
    )
    (comp (ref "P1")
      (value "CONN-TH_2P-P5.08")
      (fields (field (name "CONTRIBUTOR") "LCEDA_Lib"))
      (libsource (lib "") (part "root_2_CONN-TH_2P-P5.08__2"))
    )
    (comp (ref "P2")
      (value "CONN-TH_2P-P5.08")
      (fields (field (name "CONTRIBUTOR") "LCEDA_Lib"))
      (libsource (lib "altium-import") (part "root_2_CONN-TH_2P-P5.08_"))
    )
    (comp (ref "P3")
      (value "CONN-TH_2P-P5.08")
      (fields (field (name "CONTRIBUTOR") "LCEDA_Lib"))
      (libsource (lib "altium-import") (part "root_2_CONN-TH_2P-P5.08_"))
    )
    (comp (ref "P4")
      (value "CONN-TH_2P-P5.08")
      (fields (field (name "CONTRIBUTOR") "LCEDA_Lib"))
      (libsource (lib "") (part "root_2_CONN-TH_2P-P5.08__1"))
    )
    (comp (ref "P5")
      (value "CONN-TH_2P-P5.08")
      (fields (field (name "CONTRIBUTOR") "LCEDA_Lib"))
      (libsource (lib "") (part "root_2_CONN-TH_2P-P5.08__1"))
    )
    (comp (ref "R1")
      (value "100kΩ")
      (fields
        (field (name "MANUFACTURER") "UNI-ROYAL(厚声)")
        (field (name "MANUFACTURER PART") "0603WAF1003T5E")
      )
      (libsource (lib "altium-import") (part "root_1_100kΩ_"))
    )
    (comp (ref "R2")
      (value "13kΩ")
      (fields
        (field (name "MANUFACTURER") "UNI-ROYAL(厚声)")
        (field (name "MANUFACTURER PART") "0603WAF1302T5E")
      )
      (libsource (lib "altium-import") (part "root_1_13kΩ_"))
    )
    (comp (ref "R3")
      (value "1.3kΩ")
      (fields
        (field (name "MANUFACTURER") "UNI-ROYAL(厚声)")
        (field (name "MANUFACTURER PART") "0603WAF1301T5E")
      )
      (libsource (lib "altium-import") (part "root_0_1.3kΩ_"))
    )
    (comp (ref "R4")
      (value "1.3kΩ")
      (fields
        (field (name "MANUFACTURER") "UNI-ROYAL(厚声)")
        (field (name "MANUFACTURER PART") "0603WAF1301T5E")
      )
      (libsource (lib "altium-import") (part "root_0_1.3kΩ_"))
    )
    (comp (ref "R5")
      (value "9.1kΩ")
      (fields
        (field (name "MANUFACTURER") "UNI-ROYAL(厚声)")
        (field (name "MANUFACTURER PART") "0603WAF9101T5E")
      )
      (libsource (lib "altium-import") (part "root_0_9.1kΩ_"))
    )
    (comp (ref "R6")
      (value "9.1kΩ")
      (fields
        (field (name "MANUFACTURER") "UNI-ROYAL(厚声)")
        (field (name "MANUFACTURER PART") "0603WAF9101T5E")
      )
      (libsource (lib "altium-import") (part "root_0_9.1kΩ_"))
    )
    (comp (ref "R7")
      (value "10kΩ")
      (fields
        (field (name "MANUFACTURER") "UNI-ROYAL(厚声)")
        (field (name "MANUFACTURER PART") "0603WAF1002T5E")
      )
      (libsource (lib "altium-import") (part "root_0_10kΩ_"))
    )
    (comp (ref "R8")
      (value "10kΩ")
      (fields
        (field (name "MANUFACTURER") "UNI-ROYAL(厚声)")
        (field (name "MANUFACTURER PART") "0603WAF1002T5E")
      )
      (libsource (lib "altium-import") (part "root_0_10kΩ_"))
    )
    (comp (ref "R9")
      (value "1.8kΩ")
      (fields
        (field (name "MANUFACTURER") "UNI-ROYAL(厚声)")
        (field (name "MANUFACTURER PART") "0603WAF1801T5E")
      )
      (libsource (lib "altium-import") (part "root_1_1.8kΩ_"))
    )
    (comp (ref "R10")
      (value "1.8kΩ")
      (fields
        (field (name "MANUFACTURER") "UNI-ROYAL(厚声)")
        (field (name "MANUFACTURER PART") "0603WAF1801T5E")
      )
      (libsource (lib "altium-import") (part "root_1_1.8kΩ_"))
    )
    (comp (ref "R11")
      (value "100kΩ")
      (fields
        (field (name "MANUFACTURER") "UNI-ROYAL(厚声)")
        (field (name "MANUFACTURER PART") "0603WAF1003T5E")
      )
      (libsource (lib "altium-import") (part "root_1_100kΩ_"))
    )
    (comp (ref "R12")
      (value "100kΩ")
      (fields
        (field (name "MANUFACTURER") "UNI-ROYAL(厚声)")
        (field (name "MANUFACTURER PART") "0603WAF1003T5E")
      )
      (libsource (lib "altium-import") (part "root_1_100kΩ_"))
    )
    (comp (ref "R13")
      (value "100kΩ")
      (fields
        (field (name "MANUFACTURER") "UNI-ROYAL(厚声)")
        (field (name "MANUFACTURER PART") "0603WAF1003T5E")
      )
      (libsource (lib "altium-import") (part "root_1_100kΩ_"))
    )
    (comp (ref "R14")
      (value "100kΩ")
      (fields
        (field (name "MANUFACTURER") "UNI-ROYAL(厚声)")
        (field (name "MANUFACTURER PART") "0603WAF1003T5E")
      )
      (libsource (lib "altium-import") (part "root_1_100kΩ_"))
    )
    (comp (ref "R15")
      (value "68Ω")
      (fields
        (field (name "MANUFACTURER") "UNI-ROYAL(厚声)")
        (field (name "MANUFACTURER PART") "25121WJ0680T4E")
      )
      (libsource (lib "altium-import") (part "root_0_68Ω_"))
    )
    (comp (ref "SW1")
      (value "SKRPACE010")
      (fields (field (name "MANUFACTURER") "ALPSALPINE(阿尔卑斯阿尔派)") (field (name "CONTRIBUTOR") "LCSC"))
      (libsource (lib "altium-import") (part "root_0_SKRPACE010_"))
    )
    (comp (ref "U1")
      (value "TPS54202DDCR")
      (fields (field (name "MANUFACTURER") "TI(德州仪器)") (field (name "CONTRIBUTOR") "LCSC"))
      (libsource (lib "altium-import") (part "root_0_TPS54202DDCR_"))
    )
    (comp (ref "U2")
      (value "RP2040-ZERO")
      (fields
        (field (name "MANUFACTURER") "Waveshare(微雪电子)")
        (field (name "MANUFACTURER PART") "RP2040-Zero")
        (field (name "CONTRIBUTOR") "lcsc")
      )
      (libsource (lib "altium-import") (part "root_0_RP2040-ZERO_"))
    )
  )
  (nets
    (net (code "1") (name "+5V") (class "Default")
      (node (ref "C10") (pin "2") (pinfunction "2_2") (pintype "passive"))
      (node (ref "C11") (pin "2") (pinfunction "2_2") (pintype "passive"))
      (node (ref "C12") (pin "2") (pinfunction "2_2") (pintype "passive"))
      (node (ref "C13") (pin "2") (pinfunction "2_2") (pintype "passive"))
      (node (ref "C14") (pin "2") (pinfunction "2_2") (pintype "passive"))
      (node (ref "C15") (pin "2") (pinfunction "2_2") (pintype "passive"))
      (node (ref "C16") (pin "2") (pinfunction "2_2") (pintype "passive"))
      (node (ref "C17") (pin "2") (pinfunction "2_2") (pintype "passive"))
      (node (ref "C18") (pin "2") (pinfunction "2_2") (pintype "passive"))
      (node (ref "C19") (pin "2") (pinfunction "2_2") (pintype "passive"))
      (node (ref "C20") (pin "2") (pinfunction "2_2") (pintype "passive"))
      (node (ref "C21") (pin "2") (pinfunction "2_2") (pintype "passive"))
      (node (ref "C22") (pin "2") (pinfunction "2_2") (pintype "passive"))
      (node (ref "C23") (pin "2") (pinfunction "2_2") (pintype "passive"))
      (node (ref "C24") (pin "2") (pinfunction "2_2") (pintype "passive"))
      (node (ref "C25") (pin "2") (pinfunction "2_2") (pintype "passive"))
      (node (ref "C26") (pin "2") (pinfunction "2_2") (pintype "passive"))
      (node (ref "C27") (pin "2") (pinfunction "2_2") (pintype "passive"))
      (node (ref "C28") (pin "2") (pinfunction "2_2") (pintype "passive"))
      (node (ref "C29") (pin "2") (pinfunction "2_2") (pintype "passive"))
      (node (ref "C30") (pin "2") (pinfunction "2_2") (pintype "passive"))
      (node (ref "C31") (pin "2") (pinfunction "2_2") (pintype "passive"))
      (node (ref "C32") (pin "2") (pinfunction "2_2") (pintype "passive"))
      (node (ref "C33") (pin "2") (pinfunction "2_2") (pintype "passive"))
      (node (ref "C34") (pin "2") (pinfunction "2_2") (pintype "passive"))
      (node (ref "C35") (pin "2") (pinfunction "2_2") (pintype "passive"))
      (node (ref "C36") (pin "2") (pinfunction "2_2") (pintype "passive"))
      (node (ref "C37") (pin "2") (pinfunction "2_2") (pintype "passive"))
      (node (ref "C38") (pin "2") (pinfunction "2_2") (pintype "passive"))
      (node (ref "C39") (pin "2") (pinfunction "2_2") (pintype "passive"))
      (node (ref "C40") (pin "2") (pinfunction "2_2") (pintype "passive"))
      (node (ref "C41") (pin "2") (pinfunction "2_2") (pintype "passive"))
      (node (ref "C42") (pin "2") (pinfunction "2_2") (pintype "passive"))
      (node (ref "C43") (pin "2") (pinfunction "2_2") (pintype "passive"))
      (node (ref "C44") (pin "2") (pinfunction "2_2") (pintype "passive"))
      (node (ref "C51") (pin "2") (pinfunction "2_2") (pintype "passive"))
      (node (ref "C52") (pin "2") (pinfunction "2_2") (pintype "passive"))
      (node (ref "C53") (pin "2") (pinfunction "2_2") (pintype "passive"))
      (node (ref "C54") (pin "2") (pinfunction "2_2") (pintype "passive"))
      (node (ref "C55") (pin "2") (pinfunction "2_2") (pintype "passive"))
      (node (ref "C56") (pin "2") (pinfunction "2_2") (pintype "passive"))
      (node (ref "C57") (pin "2") (pinfunction "2_2") (pintype "passive"))
      (node (ref "C58") (pin "2") (pinfunction "2_2") (pintype "passive"))
      (node (ref "C59") (pin "2") (pinfunction "2_2") (pintype "passive"))
      (node (ref "C6") (pin "2") (pinfunction "2_2") (pintype "passive"))
      (node (ref "C60") (pin "2") (pinfunction "2_2") (pintype "passive"))
      (node (ref "C61") (pin "2") (pinfunction "2_2") (pintype "passive"))
      (node (ref "C62") (pin "2") (pinfunction "2_2") (pintype "passive"))
      (node (ref "C63") (pin "2") (pinfunction "2_2") (pintype "passive"))
      (node (ref "C64") (pin "2") (pinfunction "2_2") (pintype "passive"))
      (node (ref "C65") (pin "2") (pinfunction "2_2") (pintype "passive"))
      (node (ref "C66") (pin "2") (pinfunction "2_2") (pintype "passive"))
      (node (ref "C67") (pin "2") (pinfunction "2_2") (pintype "passive"))
      (node (ref "C68") (pin "2") (pinfunction "2_2") (pintype "passive"))
      (node (ref "C69") (pin "2") (pinfunction "2_2") (pintype "passive"))
      (node (ref "C70") (pin "2") (pinfunction "2_2") (pintype "passive"))
      (node (ref "C71") (pin "2") (pinfunction "2_2") (pintype "passive"))
      (node (ref "C72") (pin "2") (pinfunction "2_2") (pintype "passive"))
      (node (ref "C73") (pin "2") (pinfunction "2_2") (pintype "passive"))
      (node (ref "C74") (pin "2") (pinfunction "2_2") (pintype "passive"))
      (node (ref "C75") (pin "2") (pinfunction "2_2") (pintype "passive"))
      (node (ref "C76") (pin "2") (pinfunction "2_2") (pintype "passive"))
      (node (ref "C77") (pin "2") (pinfunction "2_2") (pintype "passive"))
      (node (ref "C78") (pin "2") (pinfunction "2_2") (pintype "passive"))
      (node (ref "C79") (pin "2") (pinfunction "2_2") (pintype "passive"))
      (node (ref "C80") (pin "2") (pinfunction "2_2") (pintype "passive"))
      (node (ref "C81") (pin "2") (pinfunction "2_2") (pintype "passive"))
      (node (ref "C82") (pin "2") (pinfunction "2_2") (pintype "passive"))
      (node (ref "C83") (pin "2") (pinfunction "2_2") (pintype "passive"))
      (node (ref "C84") (pin "2") (pinfunction "2_2") (pintype "passive"))
      (node (ref "C85") (pin "2") (pinfunction "2_2") (pintype "passive"))
      (node (ref "C9") (pin "2") (pinfunction "2_2") (pintype "passive"))
      (node (ref "D2") (pin "1") (pinfunction "K_1") (pintype "passive"))
      (node (ref "LED1") (pin "2") (pinfunction "VDD_2") (pintype "passive"))
      (node (ref "LED10") (pin "2") (pinfunction "VDD_2") (pintype "passive"))
      (node (ref "LED11") (pin "2") (pinfunction "VDD_2") (pintype "passive"))
      (node (ref "LED12") (pin "2") (pinfunction "VDD_2") (pintype "passive"))
      (node (ref "LED13") (pin "2") (pinfunction "VDD_2") (pintype "passive"))
      (node (ref "LED14") (pin "2") (pinfunction "VDD_2") (pintype "passive"))
      (node (ref "LED15") (pin "2") (pinfunction "VDD_2") (pintype "passive"))
      (node (ref "LED16") (pin "2") (pinfunction "VDD_2") (pintype "passive"))
      (node (ref "LED17") (pin "2") (pinfunction "VDD_2") (pintype "passive"))
      (node (ref "LED18") (pin "2") (pinfunction "VDD_2") (pintype "passive"))
      (node (ref "LED19") (pin "2") (pinfunction "VDD_2") (pintype "passive"))
      (node (ref "LED2") (pin "2") (pinfunction "VDD_2") (pintype "passive"))
      (node (ref "LED20") (pin "2") (pinfunction "VDD_2") (pintype "passive"))
      (node (ref "LED21") (pin "2") (pinfunction "VDD_2") (pintype "passive"))
      (node (ref "LED22") (pin "2") (pinfunction "VDD_2") (pintype "passive"))
      (node (ref "LED23") (pin "2") (pinfunction "VDD_2") (pintype "passive"))
      (node (ref "LED24") (pin "2") (pinfunction "VDD_2") (pintype "passive"))
      (node (ref "LED25") (pin "2") (pinfunction "VDD_2") (pintype "passive"))
      (node (ref "LED26") (pin "2") (pinfunction "VDD_2") (pintype "passive"))
      (node (ref "LED27") (pin "2") (pinfunction "VDD_2") (pintype "passive"))
      (node (ref "LED28") (pin "2") (pinfunction "VDD_2") (pintype "passive"))
      (node (ref "LED29") (pin "2") (pinfunction "VDD_2") (pintype "passive"))
      (node (ref "LED3") (pin "2") (pinfunction "VDD_2") (pintype "passive"))
      (node (ref "LED30") (pin "2") (pinfunction "VDD_2") (pintype "passive"))
      (node (ref "LED31") (pin "2") (pinfunction "VDD_2") (pintype "passive"))
      (node (ref "LED32") (pin "2") (pinfunction "VDD_2") (pintype "passive"))
      (node (ref "LED33") (pin "2") (pinfunction "VDD_2") (pintype "passive"))
      (node (ref "LED34") (pin "2") (pinfunction "VDD_2") (pintype "passive"))
      (node (ref "LED35") (pin "2") (pinfunction "VDD_2") (pintype "passive"))
      (node (ref "LED36") (pin "2") (pinfunction "VDD_2") (pintype "passive"))
      (node (ref "LED4") (pin "2") (pinfunction "VDD_2") (pintype "passive"))
      (node (ref "LED43") (pin "2") (pinfunction "VDD_2") (pintype "passive"))
      (node (ref "LED44") (pin "2") (pinfunction "VDD_2") (pintype "passive"))
      (node (ref "LED45") (pin "2") (pinfunction "VDD_2") (pintype "passive"))
      (node (ref "LED46") (pin "2") (pinfunction "VDD_2") (pintype "passive"))
      (node (ref "LED47") (pin "2") (pinfunction "VDD_2") (pintype "passive"))
      (node (ref "LED48") (pin "2") (pinfunction "VDD_2") (pintype "passive"))
      (node (ref "LED49") (pin "2") (pinfunction "VDD_2") (pintype "passive"))
      (node (ref "LED5") (pin "2") (pinfunction "VDD_2") (pintype "passive"))
      (node (ref "LED50") (pin "2") (pinfunction "VDD_2") (pintype "passive"))
      (node (ref "LED51") (pin "2") (pinfunction "VDD_2") (pintype "passive"))
      (node (ref "LED52") (pin "2") (pinfunction "VDD_2") (pintype "passive"))
      (node (ref "LED53") (pin "2") (pinfunction "VDD_2") (pintype "passive"))
      (node (ref "LED54") (pin "2") (pinfunction "VDD_2") (pintype "passive"))
      (node (ref "LED55") (pin "2") (pinfunction "VDD_2") (pintype "passive"))
      (node (ref "LED56") (pin "2") (pinfunction "VDD_2") (pintype "passive"))
      (node (ref "LED57") (pin "2") (pinfunction "VDD_2") (pintype "passive"))
      (node (ref "LED58") (pin "2") (pinfunction "VDD_2") (pintype "passive"))
      (node (ref "LED59") (pin "2") (pinfunction "VDD_2") (pintype "passive"))
      (node (ref "LED6") (pin "2") (pinfunction "VDD_2") (pintype "passive"))
      (node (ref "LED60") (pin "2") (pinfunction "VDD_2") (pintype "passive"))
      (node (ref "LED61") (pin "2") (pinfunction "VDD_2") (pintype "passive"))
      (node (ref "LED62") (pin "2") (pinfunction "VDD_2") (pintype "passive"))
      (node (ref "LED63") (pin "2") (pinfunction "VDD_2") (pintype "passive"))
      (node (ref "LED64") (pin "2") (pinfunction "VDD_2") (pintype "passive"))
      (node (ref "LED65") (pin "2") (pinfunction "VDD_2") (pintype "passive"))
      (node (ref "LED66") (pin "2") (pinfunction "VDD_2") (pintype "passive"))
      (node (ref "LED67") (pin "2") (pinfunction "VDD_2") (pintype "passive"))
      (node (ref "LED68") (pin "2") (pinfunction "VDD_2") (pintype "passive"))
      (node (ref "LED69") (pin "2") (pinfunction "VDD_2") (pintype "passive"))
      (node (ref "LED7") (pin "2") (pinfunction "VDD_2") (pintype "passive"))
      (node (ref "LED70") (pin "2") (pinfunction "VDD_2") (pintype "passive"))
      (node (ref "LED71") (pin "2") (pinfunction "VDD_2") (pintype "passive"))
      (node (ref "LED72") (pin "2") (pinfunction "VDD_2") (pintype "passive"))
      (node (ref "LED73") (pin "2") (pinfunction "VDD_2") (pintype "passive"))
      (node (ref "LED74") (pin "2") (pinfunction "VDD_2") (pintype "passive"))
      (node (ref "LED75") (pin "2") (pinfunction "VDD_2") (pintype "passive"))
      (node (ref "LED76") (pin "2") (pinfunction "VDD_2") (pintype "passive"))
      (node (ref "LED77") (pin "2") (pinfunction "VDD_2") (pintype "passive"))
      (node (ref "LED78") (pin "2") (pinfunction "VDD_2") (pintype "passive"))
      (node (ref "LED8") (pin "2") (pinfunction "VDD_2") (pintype "passive"))
      (node (ref "LED9") (pin "2") (pinfunction "VDD_2") (pintype "passive"))
      (node (ref "U2") (pin "23") (pinfunction "5V_23") (pintype "passive"))
    )
    (net (code "2") (name "/3V3") (class "Default")
      (node (ref "R11") (pin "2") (pinfunction "2_2") (pintype "passive"))
      (node (ref "R13") (pin "2") (pinfunction "2_2") (pintype "passive"))
      (node (ref "U2") (pin "21") (pinfunction "3V3_21") (pintype "passive"))
    )
    (net (code "3") (name "/LEFT") (class "Default")
      (node (ref "LED1") (pin "1") (pinfunction "DIN_1") (pintype "passive"))
      (node (ref "U2") (pin "15") (pinfunction "GP14_15") (pintype "passive"))
    )
    (net (code "4") (name "/RIGHT") (class "Default")
      (node (ref "LED43") (pin "1") (pinfunction "DIN_1") (pintype "passive"))
      (node (ref "U2") (pin "16") (pinfunction "GP15_16") (pintype "passive"))
    )
    (net (code "5") (name "GND") (class "Default")
      (node (ref "C1") (pin "1") (pinfunction "1_1") (pintype "passive"))
      (node (ref "C10") (pin "1") (pinfunction "1_1") (pintype "passive"))
      (node (ref "C11") (pin "1") (pinfunction "1_1") (pintype "passive"))
      (node (ref "C12") (pin "1") (pinfunction "1_1") (pintype "passive"))
      (node (ref "C13") (pin "1") (pinfunction "1_1") (pintype "passive"))
      (node (ref "C14") (pin "1") (pinfunction "1_1") (pintype "passive"))
      (node (ref "C15") (pin "1") (pinfunction "1_1") (pintype "passive"))
      (node (ref "C16") (pin "1") (pinfunction "1_1") (pintype "passive"))
      (node (ref "C17") (pin "1") (pinfunction "1_1") (pintype "passive"))
      (node (ref "C18") (pin "1") (pinfunction "1_1") (pintype "passive"))
      (node (ref "C19") (pin "1") (pinfunction "1_1") (pintype "passive"))
      (node (ref "C20") (pin "1") (pinfunction "1_1") (pintype "passive"))
      (node (ref "C21") (pin "1") (pinfunction "1_1") (pintype "passive"))
      (node (ref "C22") (pin "1") (pinfunction "1_1") (pintype "passive"))
      (node (ref "C23") (pin "1") (pinfunction "1_1") (pintype "passive"))
      (node (ref "C24") (pin "1") (pinfunction "1_1") (pintype "passive"))
      (node (ref "C25") (pin "1") (pinfunction "1_1") (pintype "passive"))
      (node (ref "C26") (pin "1") (pinfunction "1_1") (pintype "passive"))
      (node (ref "C27") (pin "1") (pinfunction "1_1") (pintype "passive"))
      (node (ref "C28") (pin "1") (pinfunction "1_1") (pintype "passive"))
      (node (ref "C29") (pin "1") (pinfunction "1_1") (pintype "passive"))
      (node (ref "C30") (pin "1") (pinfunction "1_1") (pintype "passive"))
      (node (ref "C31") (pin "1") (pinfunction "1_1") (pintype "passive"))
      (node (ref "C32") (pin "1") (pinfunction "1_1") (pintype "passive"))
      (node (ref "C33") (pin "1") (pinfunction "1_1") (pintype "passive"))
      (node (ref "C34") (pin "1") (pinfunction "1_1") (pintype "passive"))
      (node (ref "C35") (pin "1") (pinfunction "1_1") (pintype "passive"))
      (node (ref "C36") (pin "1") (pinfunction "1_1") (pintype "passive"))
      (node (ref "C37") (pin "1") (pinfunction "1_1") (pintype "passive"))
      (node (ref "C38") (pin "1") (pinfunction "1_1") (pintype "passive"))
      (node (ref "C39") (pin "1") (pinfunction "1_1") (pintype "passive"))
      (node (ref "C4") (pin "1") (pinfunction "1_1") (pintype "passive"))
      (node (ref "C40") (pin "1") (pinfunction "1_1") (pintype "passive"))
      (node (ref "C41") (pin "1") (pinfunction "1_1") (pintype "passive"))
      (node (ref "C42") (pin "1") (pinfunction "1_1") (pintype "passive"))
      (node (ref "C43") (pin "1") (pinfunction "1_1") (pintype "passive"))
      (node (ref "C44") (pin "1") (pinfunction "1_1") (pintype "passive"))
      (node (ref "C47") (pin "1") (pinfunction "1_1") (pintype "passive"))
      (node (ref "C48") (pin "1") (pinfunction "1_1") (pintype "passive"))
      (node (ref "C49") (pin "2") (pinfunction "2_2") (pintype "passive"))
      (node (ref "C5") (pin "1") (pinfunction "1_1") (pintype "passive"))
      (node (ref "C50") (pin "2") (pinfunction "2_2") (pintype "passive"))
      (node (ref "C51") (pin "1") (pinfunction "1_1") (pintype "passive"))
      (node (ref "C52") (pin "1") (pinfunction "1_1") (pintype "passive"))
      (node (ref "C53") (pin "1") (pinfunction "1_1") (pintype "passive"))
      (node (ref "C54") (pin "1") (pinfunction "1_1") (pintype "passive"))
      (node (ref "C55") (pin "1") (pinfunction "1_1") (pintype "passive"))
      (node (ref "C56") (pin "1") (pinfunction "1_1") (pintype "passive"))
      (node (ref "C57") (pin "1") (pinfunction "1_1") (pintype "passive"))
      (node (ref "C58") (pin "1") (pinfunction "1_1") (pintype "passive"))
      (node (ref "C59") (pin "1") (pinfunction "1_1") (pintype "passive"))
      (node (ref "C6") (pin "1") (pinfunction "1_1") (pintype "passive"))
      (node (ref "C60") (pin "1") (pinfunction "1_1") (pintype "passive"))
      (node (ref "C61") (pin "1") (pinfunction "1_1") (pintype "passive"))
      (node (ref "C62") (pin "1") (pinfunction "1_1") (pintype "passive"))
      (node (ref "C63") (pin "1") (pinfunction "1_1") (pintype "passive"))
      (node (ref "C64") (pin "1") (pinfunction "1_1") (pintype "passive"))
      (node (ref "C65") (pin "1") (pinfunction "1_1") (pintype "passive"))
      (node (ref "C66") (pin "1") (pinfunction "1_1") (pintype "passive"))
      (node (ref "C67") (pin "1") (pinfunction "1_1") (pintype "passive"))
      (node (ref "C68") (pin "1") (pinfunction "1_1") (pintype "passive"))
      (node (ref "C69") (pin "1") (pinfunction "1_1") (pintype "passive"))
      (node (ref "C7") (pin "1") (pinfunction "1_1") (pintype "passive"))
      (node (ref "C70") (pin "1") (pinfunction "1_1") (pintype "passive"))
      (node (ref "C71") (pin "1") (pinfunction "1_1") (pintype "passive"))
      (node (ref "C72") (pin "1") (pinfunction "1_1") (pintype "passive"))
      (node (ref "C73") (pin "1") (pinfunction "1_1") (pintype "passive"))
      (node (ref "C74") (pin "1") (pinfunction "1_1") (pintype "passive"))
      (node (ref "C75") (pin "1") (pinfunction "1_1") (pintype "passive"))
      (node (ref "C76") (pin "1") (pinfunction "1_1") (pintype "passive"))
      (node (ref "C77") (pin "1") (pinfunction "1_1") (pintype "passive"))
      (node (ref "C78") (pin "1") (pinfunction "1_1") (pintype "passive"))
      (node (ref "C79") (pin "1") (pinfunction "1_1") (pintype "passive"))
      (node (ref "C8") (pin "1") (pinfunction "1_1") (pintype "passive"))
      (node (ref "C80") (pin "1") (pinfunction "1_1") (pintype "passive"))
      (node (ref "C81") (pin "1") (pinfunction "1_1") (pintype "passive"))
      (node (ref "C82") (pin "1") (pinfunction "1_1") (pintype "passive"))
      (node (ref "C83") (pin "1") (pinfunction "1_1") (pintype "passive"))
      (node (ref "C84") (pin "1") (pinfunction "1_1") (pintype "passive"))
      (node (ref "C85") (pin "1") (pinfunction "1_1") (pintype "passive"))
      (node (ref "C86") (pin "2") (pinfunction "2_2") (pintype "passive"))
      (node (ref "C9") (pin "1") (pinfunction "1_1") (pintype "passive"))
      (node (ref "LED1") (pin "4") (pinfunction "VSS_4") (pintype "passive"))
      (node (ref "LED10") (pin "4") (pinfunction "VSS_4") (pintype "passive"))
      (node (ref "LED11") (pin "4") (pinfunction "VSS_4") (pintype "passive"))
      (node (ref "LED12") (pin "4") (pinfunction "VSS_4") (pintype "passive"))
      (node (ref "LED13") (pin "4") (pinfunction "VSS_4") (pintype "passive"))
      (node (ref "LED14") (pin "4") (pinfunction "VSS_4") (pintype "passive"))
      (node (ref "LED15") (pin "4") (pinfunction "VSS_4") (pintype "passive"))
      (node (ref "LED16") (pin "4") (pinfunction "VSS_4") (pintype "passive"))
      (node (ref "LED17") (pin "4") (pinfunction "VSS_4") (pintype "passive"))
      (node (ref "LED18") (pin "4") (pinfunction "VSS_4") (pintype "passive"))
      (node (ref "LED19") (pin "4") (pinfunction "VSS_4") (pintype "passive"))
      (node (ref "LED2") (pin "4") (pinfunction "VSS_4") (pintype "passive"))
      (node (ref "LED20") (pin "4") (pinfunction "VSS_4") (pintype "passive"))
      (node (ref "LED21") (pin "4") (pinfunction "VSS_4") (pintype "passive"))
      (node (ref "LED22") (pin "4") (pinfunction "VSS_4") (pintype "passive"))
      (node (ref "LED23") (pin "4") (pinfunction "VSS_4") (pintype "passive"))
      (node (ref "LED24") (pin "4") (pinfunction "VSS_4") (pintype "passive"))
      (node (ref "LED25") (pin "4") (pinfunction "VSS_4") (pintype "passive"))
      (node (ref "LED26") (pin "4") (pinfunction "VSS_4") (pintype "passive"))
      (node (ref "LED27") (pin "4") (pinfunction "VSS_4") (pintype "passive"))
      (node (ref "LED28") (pin "4") (pinfunction "VSS_4") (pintype "passive"))
      (node (ref "LED29") (pin "4") (pinfunction "VSS_4") (pintype "passive"))
      (node (ref "LED3") (pin "4") (pinfunction "VSS_4") (pintype "passive"))
      (node (ref "LED30") (pin "4") (pinfunction "VSS_4") (pintype "passive"))
      (node (ref "LED31") (pin "4") (pinfunction "VSS_4") (pintype "passive"))
      (node (ref "LED32") (pin "4") (pinfunction "VSS_4") (pintype "passive"))
      (node (ref "LED33") (pin "4") (pinfunction "VSS_4") (pintype "passive"))
      (node (ref "LED34") (pin "4") (pinfunction "VSS_4") (pintype "passive"))
      (node (ref "LED35") (pin "4") (pinfunction "VSS_4") (pintype "passive"))
      (node (ref "LED36") (pin "4") (pinfunction "VSS_4") (pintype "passive"))
      (node (ref "LED4") (pin "4") (pinfunction "VSS_4") (pintype "passive"))
      (node (ref "LED43") (pin "4") (pinfunction "VSS_4") (pintype "passive"))
      (node (ref "LED44") (pin "4") (pinfunction "VSS_4") (pintype "passive"))
      (node (ref "LED45") (pin "4") (pinfunction "VSS_4") (pintype "passive"))
      (node (ref "LED46") (pin "4") (pinfunction "VSS_4") (pintype "passive"))
      (node (ref "LED47") (pin "4") (pinfunction "VSS_4") (pintype "passive"))
      (node (ref "LED48") (pin "4") (pinfunction "VSS_4") (pintype "passive"))
      (node (ref "LED49") (pin "4") (pinfunction "VSS_4") (pintype "passive"))
      (node (ref "LED5") (pin "4") (pinfunction "VSS_4") (pintype "passive"))
      (node (ref "LED50") (pin "4") (pinfunction "VSS_4") (pintype "passive"))
      (node (ref "LED51") (pin "4") (pinfunction "VSS_4") (pintype "passive"))
      (node (ref "LED52") (pin "4") (pinfunction "VSS_4") (pintype "passive"))
      (node (ref "LED53") (pin "4") (pinfunction "VSS_4") (pintype "passive"))
      (node (ref "LED54") (pin "4") (pinfunction "VSS_4") (pintype "passive"))
      (node (ref "LED55") (pin "4") (pinfunction "VSS_4") (pintype "passive"))
      (node (ref "LED56") (pin "4") (pinfunction "VSS_4") (pintype "passive"))
      (node (ref "LED57") (pin "4") (pinfunction "VSS_4") (pintype "passive"))
      (node (ref "LED58") (pin "4") (pinfunction "VSS_4") (pintype "passive"))
      (node (ref "LED59") (pin "4") (pinfunction "VSS_4") (pintype "passive"))
      (node (ref "LED6") (pin "4") (pinfunction "VSS_4") (pintype "passive"))
      (node (ref "LED60") (pin "4") (pinfunction "VSS_4") (pintype "passive"))
      (node (ref "LED61") (pin "4") (pinfunction "VSS_4") (pintype "passive"))
      (node (ref "LED62") (pin "4") (pinfunction "VSS_4") (pintype "passive"))
      (node (ref "LED63") (pin "4") (pinfunction "VSS_4") (pintype "passive"))
      (node (ref "LED64") (pin "4") (pinfunction "VSS_4") (pintype "passive"))
      (node (ref "LED65") (pin "4") (pinfunction "VSS_4") (pintype "passive"))
      (node (ref "LED66") (pin "4") (pinfunction "VSS_4") (pintype "passive"))
      (node (ref "LED67") (pin "4") (pinfunction "VSS_4") (pintype "passive"))
      (node (ref "LED68") (pin "4") (pinfunction "VSS_4") (pintype "passive"))
      (node (ref "LED69") (pin "4") (pinfunction "VSS_4") (pintype "passive"))
      (node (ref "LED7") (pin "4") (pinfunction "VSS_4") (pintype "passive"))
      (node (ref "LED70") (pin "4") (pinfunction "VSS_4") (pintype "passive"))
      (node (ref "LED71") (pin "4") (pinfunction "VSS_4") (pintype "passive"))
      (node (ref "LED72") (pin "4") (pinfunction "VSS_4") (pintype "passive"))
      (node (ref "LED73") (pin "4") (pinfunction "VSS_4") (pintype "passive"))
      (node (ref "LED74") (pin "4") (pinfunction "VSS_4") (pintype "passive"))
      (node (ref "LED75") (pin "4") (pinfunction "VSS_4") (pintype "passive"))
      (node (ref "LED76") (pin "4") (pinfunction "VSS_4") (pintype "passive"))
      (node (ref "LED77") (pin "4") (pinfunction "VSS_4") (pintype "passive"))
      (node (ref "LED78") (pin "4") (pinfunction "VSS_4") (pintype "passive"))
      (node (ref "LED8") (pin "4") (pinfunction "VSS_4") (pintype "passive"))
      (node (ref "LED9") (pin "4") (pinfunction "VSS_4") (pintype "passive"))
      (node (ref "P1") (pin "1") (pinfunction "1_1") (pintype "passive"))
      (node (ref "P4") (pin "1") (pinfunction "1_1") (pintype "passive"))
      (node (ref "P5") (pin "1") (pinfunction "1_1") (pintype "passive"))
      (node (ref "R10") (pin "1") (pinfunction "1_1") (pintype "passive"))
      (node (ref "R12") (pin "1") (pinfunction "1_1") (pintype "passive"))
      (node (ref "R14") (pin "1") (pinfunction "1_1") (pintype "passive"))
      (node (ref "R2") (pin "1") (pinfunction "1_1") (pintype "passive"))
      (node (ref "R9") (pin "1") (pinfunction "1_1") (pintype "passive"))
      (node (ref "SW1") (pin "3") (pinfunction "3_3") (pintype "passive"))
      (node (ref "SW1") (pin "4") (pinfunction "4_4") (pintype "passive"))
      (node (ref "U1") (pin "1") (pinfunction "GND_1") (pintype "passive"))
      (node (ref "U2") (pin "22") (pinfunction "GND_22") (pintype "passive"))
    )
    (net (code "6") (name "Net-(C45-Pad1)") (class "Default")
      (node (ref "C45") (pin "1") (pinfunction "1_1") (pintype "passive"))
      (node (ref "P2") (pin "2") (pinfunction "2_2") (pintype "passive"))
      (node (ref "R3") (pin "2") (pinfunction "2_2") (pintype "passive"))
    )
    (net (code "7") (name "Net-(C45-Pad2)") (class "Default")
      (node (ref "C45") (pin "2") (pinfunction "2_2") (pintype "passive"))
      (node (ref "C49") (pin "1") (pinfunction "1_1") (pintype "passive"))
      (node (ref "R5") (pin "1") (pinfunction "1_1") (pintype "passive"))
    )
    (net (code "8") (name "Net-(C46-Pad1)") (class "Default")
      (node (ref "C46") (pin "1") (pinfunction "1_1") (pintype "passive"))
      (node (ref "P3") (pin "1") (pinfunction "1_1") (pintype "passive"))
      (node (ref "R4") (pin "2") (pinfunction "2_2") (pintype "passive"))
    )
    (net (code "9") (name "Net-(C46-Pad2)") (class "Default")
      (node (ref "C46") (pin "2") (pinfunction "2_2") (pintype "passive"))
      (node (ref "C50") (pin "1") (pinfunction "1_1") (pintype "passive"))
      (node (ref "R6") (pin "1") (pinfunction "1_1") (pintype "passive"))
    )
    (net (code "10") (name "Net-(D1-A)") (class "Default")
      (node (ref "D1") (pin "2") (pinfunction "A_2") (pintype "passive"))
      (node (ref "P1") (pin "2") (pinfunction "2_2") (pintype "passive"))
    )
    (net (code "11") (name "Net-(D1-K)") (class "Default")
      (node (ref "D1") (pin "1") (pinfunction "K_1") (pintype "passive"))
      (node (ref "R15") (pin "1") (pinfunction "1_1") (pintype "passive"))
    )
    (net (code "12") (name "Net-(D2-A)") (class "Default")
      (node (ref "C3") (pin "2") (pinfunction "2_2") (pintype "passive"))
      (node (ref "C4") (pin "2") (pinfunction "2_2") (pintype "passive"))
      (node (ref "C5") (pin "2") (pinfunction "2_2") (pintype "passive"))
      (node (ref "D2") (pin "2") (pinfunction "A_2") (pintype "passive"))
      (node (ref "L1") (pin "2") (pinfunction "2_2") (pintype "passive"))
      (node (ref "R1") (pin "2") (pinfunction "2_2") (pintype "passive"))
    )
    (net (code "13") (name "Net-(LED1-DOUT)") (class "Default")
      (node (ref "LED1") (pin "3") (pinfunction "DOUT_3") (pintype "passive"))
      (node (ref "LED2") (pin "1") (pinfunction "DIN_1") (pintype "passive"))
    )
    (net (code "14") (name "Net-(LED2-DOUT)") (class "Default")
      (node (ref "LED2") (pin "3") (pinfunction "DOUT_3") (pintype "passive"))
      (node (ref "LED3") (pin "1") (pinfunction "DIN_1") (pintype "passive"))
    )
    (net (code "15") (name "Net-(LED3-DOUT)") (class "Default")
      (node (ref "LED3") (pin "3") (pinfunction "DOUT_3") (pintype "passive"))
      (node (ref "LED4") (pin "1") (pinfunction "DIN_1") (pintype "passive"))
    )
    (net (code "16") (name "Net-(LED4-DOUT)") (class "Default")
      (node (ref "LED4") (pin "3") (pinfunction "DOUT_3") (pintype "passive"))
      (node (ref "LED5") (pin "1") (pinfunction "DIN_1") (pintype "passive"))
    )
    (net (code "17") (name "Net-(LED5-DOUT)") (class "Default")
      (node (ref "LED5") (pin "3") (pinfunction "DOUT_3") (pintype "passive"))
      (node (ref "LED6") (pin "1") (pinfunction "DIN_1") (pintype "passive"))
    )
    (net (code "18") (name "Net-(LED6-DOUT)") (class "Default")
      (node (ref "LED6") (pin "3") (pinfunction "DOUT_3") (pintype "passive"))
      (node (ref "LED7") (pin "1") (pinfunction "DIN_1") (pintype "passive"))
    )
    (net (code "19") (name "Net-(LED7-DOUT)") (class "Default")
      (node (ref "LED7") (pin "3") (pinfunction "DOUT_3") (pintype "passive"))
      (node (ref "LED8") (pin "1") (pinfunction "DIN_1") (pintype "passive"))
    )
    (net (code "20") (name "Net-(LED8-DOUT)") (class "Default")
      (node (ref "LED8") (pin "3") (pinfunction "DOUT_3") (pintype "passive"))
      (node (ref "LED9") (pin "1") (pinfunction "DIN_1") (pintype "passive"))
    )
    (net (code "21") (name "Net-(LED10-DIN)") (class "Default")
      (node (ref "LED10") (pin "1") (pinfunction "DIN_1") (pintype "passive"))
      (node (ref "LED9") (pin "3") (pinfunction "DOUT_3") (pintype "passive"))
    )
    (net (code "22") (name "Net-(LED10-DOUT)") (class "Default")
      (node (ref "LED10") (pin "3") (pinfunction "DOUT_3") (pintype "passive"))
      (node (ref "LED11") (pin "1") (pinfunction "DIN_1") (pintype "passive"))
    )
    (net (code "23") (name "Net-(LED11-DOUT)") (class "Default")
      (node (ref "LED11") (pin "3") (pinfunction "DOUT_3") (pintype "passive"))
      (node (ref "LED12") (pin "1") (pinfunction "DIN_1") (pintype "passive"))
    )
    (net (code "24") (name "Net-(LED12-DOUT)") (class "Default")
      (node (ref "LED12") (pin "3") (pinfunction "DOUT_3") (pintype "passive"))
      (node (ref "LED13") (pin "1") (pinfunction "DIN_1") (pintype "passive"))
    )
    (net (code "25") (name "Net-(LED13-DOUT)") (class "Default")
      (node (ref "LED13") (pin "3") (pinfunction "DOUT_3") (pintype "passive"))
      (node (ref "LED14") (pin "1") (pinfunction "DIN_1") (pintype "passive"))
    )
    (net (code "26") (name "Net-(LED14-DOUT)") (class "Default")
      (node (ref "LED14") (pin "3") (pinfunction "DOUT_3") (pintype "passive"))
      (node (ref "LED15") (pin "1") (pinfunction "DIN_1") (pintype "passive"))
    )
    (net (code "27") (name "Net-(LED15-DOUT)") (class "Default")
      (node (ref "LED15") (pin "3") (pinfunction "DOUT_3") (pintype "passive"))
      (node (ref "LED16") (pin "1") (pinfunction "DIN_1") (pintype "passive"))
    )
    (net (code "28") (name "Net-(LED16-DOUT)") (class "Default")
      (node (ref "LED16") (pin "3") (pinfunction "DOUT_3") (pintype "passive"))
      (node (ref "LED17") (pin "1") (pinfunction "DIN_1") (pintype "passive"))
    )
    (net (code "29") (name "Net-(LED17-DOUT)") (class "Default")
      (node (ref "LED17") (pin "3") (pinfunction "DOUT_3") (pintype "passive"))
      (node (ref "LED18") (pin "1") (pinfunction "DIN_1") (pintype "passive"))
    )
    (net (code "30") (name "Net-(LED18-DOUT)") (class "Default")
      (node (ref "LED18") (pin "3") (pinfunction "DOUT_3") (pintype "passive"))
      (node (ref "LED19") (pin "1") (pinfunction "DIN_1") (pintype "passive"))
    )
    (net (code "31") (name "Net-(LED19-DOUT)") (class "Default")
      (node (ref "LED19") (pin "3") (pinfunction "DOUT_3") (pintype "passive"))
      (node (ref "LED20") (pin "1") (pinfunction "DIN_1") (pintype "passive"))
    )
    (net (code "32") (name "Net-(LED20-DOUT)") (class "Default")
      (node (ref "LED20") (pin "3") (pinfunction "DOUT_3") (pintype "passive"))
      (node (ref "LED21") (pin "1") (pinfunction "DIN_1") (pintype "passive"))
    )
    (net (code "33") (name "Net-(LED21-DOUT)") (class "Default")
      (node (ref "LED21") (pin "3") (pinfunction "DOUT_3") (pintype "passive"))
      (node (ref "LED22") (pin "1") (pinfunction "DIN_1") (pintype "passive"))
    )
    (net (code "34") (name "Net-(LED22-DOUT)") (class "Default")
      (node (ref "LED22") (pin "3") (pinfunction "DOUT_3") (pintype "passive"))
      (node (ref "LED23") (pin "1") (pinfunction "DIN_1") (pintype "passive"))
    )
    (net (code "35") (name "Net-(LED23-DOUT)") (class "Default")
      (node (ref "LED23") (pin "3") (pinfunction "DOUT_3") (pintype "passive"))
      (node (ref "LED24") (pin "1") (pinfunction "DIN_1") (pintype "passive"))
    )
    (net (code "36") (name "Net-(LED24-DOUT)") (class "Default")
      (node (ref "LED24") (pin "3") (pinfunction "DOUT_3") (pintype "passive"))
      (node (ref "LED25") (pin "1") (pinfunction "DIN_1") (pintype "passive"))
    )
    (net (code "37") (name "Net-(LED25-DOUT)") (class "Default")
      (node (ref "LED25") (pin "3") (pinfunction "DOUT_3") (pintype "passive"))
      (node (ref "LED26") (pin "1") (pinfunction "DIN_1") (pintype "passive"))
    )
    (net (code "38") (name "Net-(LED26-DOUT)") (class "Default")
      (node (ref "LED26") (pin "3") (pinfunction "DOUT_3") (pintype "passive"))
      (node (ref "LED27") (pin "1") (pinfunction "DIN_1") (pintype "passive"))
    )
    (net (code "39") (name "Net-(LED27-DOUT)") (class "Default")
      (node (ref "LED27") (pin "3") (pinfunction "DOUT_3") (pintype "passive"))
      (node (ref "LED28") (pin "1") (pinfunction "DIN_1") (pintype "passive"))
    )
    (net (code "40") (name "Net-(LED28-DOUT)") (class "Default")
      (node (ref "LED28") (pin "3") (pinfunction "DOUT_3") (pintype "passive"))
      (node (ref "LED29") (pin "1") (pinfunction "DIN_1") (pintype "passive"))
    )
    (net (code "41") (name "Net-(LED29-DOUT)") (class "Default")
      (node (ref "LED29") (pin "3") (pinfunction "DOUT_3") (pintype "passive"))
      (node (ref "LED30") (pin "1") (pinfunction "DIN_1") (pintype "passive"))
    )
    (net (code "42") (name "Net-(LED30-DOUT)") (class "Default")
      (node (ref "LED30") (pin "3") (pinfunction "DOUT_3") (pintype "passive"))
      (node (ref "LED31") (pin "1") (pinfunction "DIN_1") (pintype "passive"))
    )
    (net (code "43") (name "Net-(LED31-DOUT)") (class "Default")
      (node (ref "LED31") (pin "3") (pinfunction "DOUT_3") (pintype "passive"))
      (node (ref "LED32") (pin "1") (pinfunction "DIN_1") (pintype "passive"))
    )
    (net (code "44") (name "Net-(LED32-DOUT)") (class "Default")
      (node (ref "LED32") (pin "3") (pinfunction "DOUT_3") (pintype "passive"))
      (node (ref "LED33") (pin "1") (pinfunction "DIN_1") (pintype "passive"))
    )
    (net (code "45") (name "Net-(LED33-DOUT)") (class "Default")
      (node (ref "LED33") (pin "3") (pinfunction "DOUT_3") (pintype "passive"))
      (node (ref "LED34") (pin "1") (pinfunction "DIN_1") (pintype "passive"))
    )
    (net (code "46") (name "Net-(LED34-DOUT)") (class "Default")
      (node (ref "LED34") (pin "3") (pinfunction "DOUT_3") (pintype "passive"))
      (node (ref "LED35") (pin "1") (pinfunction "DIN_1") (pintype "passive"))
    )
    (net (code "47") (name "Net-(LED35-DOUT)") (class "Default")
      (node (ref "LED35") (pin "3") (pinfunction "DOUT_3") (pintype "passive"))
      (node (ref "LED36") (pin "1") (pinfunction "DIN_1") (pintype "passive"))
    )
    (net (code "48") (name "Net-(LED43-DOUT)") (class "Default")
      (node (ref "LED43") (pin "3") (pinfunction "DOUT_3") (pintype "passive"))
      (node (ref "LED44") (pin "1") (pinfunction "DIN_1") (pintype "passive"))
    )
    (net (code "49") (name "Net-(LED44-DOUT)") (class "Default")
      (node (ref "LED44") (pin "3") (pinfunction "DOUT_3") (pintype "passive"))
      (node (ref "LED45") (pin "1") (pinfunction "DIN_1") (pintype "passive"))
    )
    (net (code "50") (name "Net-(LED45-DOUT)") (class "Default")
      (node (ref "LED45") (pin "3") (pinfunction "DOUT_3") (pintype "passive"))
      (node (ref "LED46") (pin "1") (pinfunction "DIN_1") (pintype "passive"))
    )
    (net (code "51") (name "Net-(LED46-DOUT)") (class "Default")
      (node (ref "LED46") (pin "3") (pinfunction "DOUT_3") (pintype "passive"))
      (node (ref "LED47") (pin "1") (pinfunction "DIN_1") (pintype "passive"))
    )
    (net (code "52") (name "Net-(LED47-DOUT)") (class "Default")
      (node (ref "LED47") (pin "3") (pinfunction "DOUT_3") (pintype "passive"))
      (node (ref "LED48") (pin "1") (pinfunction "DIN_1") (pintype "passive"))
    )
    (net (code "53") (name "Net-(LED48-DOUT)") (class "Default")
      (node (ref "LED48") (pin "3") (pinfunction "DOUT_3") (pintype "passive"))
      (node (ref "LED49") (pin "1") (pinfunction "DIN_1") (pintype "passive"))
    )
    (net (code "54") (name "Net-(LED49-DOUT)") (class "Default")
      (node (ref "LED49") (pin "3") (pinfunction "DOUT_3") (pintype "passive"))
      (node (ref "LED50") (pin "1") (pinfunction "DIN_1") (pintype "passive"))
    )
    (net (code "55") (name "Net-(LED50-DOUT)") (class "Default")
      (node (ref "LED50") (pin "3") (pinfunction "DOUT_3") (pintype "passive"))
      (node (ref "LED51") (pin "1") (pinfunction "DIN_1") (pintype "passive"))
    )
    (net (code "56") (name "Net-(LED51-DOUT)") (class "Default")
      (node (ref "LED51") (pin "3") (pinfunction "DOUT_3") (pintype "passive"))
      (node (ref "LED52") (pin "1") (pinfunction "DIN_1") (pintype "passive"))
    )
    (net (code "57") (name "Net-(LED52-DOUT)") (class "Default")
      (node (ref "LED52") (pin "3") (pinfunction "DOUT_3") (pintype "passive"))
      (node (ref "LED53") (pin "1") (pinfunction "DIN_1") (pintype "passive"))
    )
    (net (code "58") (name "Net-(LED53-DOUT)") (class "Default")
      (node (ref "LED53") (pin "3") (pinfunction "DOUT_3") (pintype "passive"))
      (node (ref "LED54") (pin "1") (pinfunction "DIN_1") (pintype "passive"))
    )
    (net (code "59") (name "Net-(LED54-DOUT)") (class "Default")
      (node (ref "LED54") (pin "3") (pinfunction "DOUT_3") (pintype "passive"))
      (node (ref "LED55") (pin "1") (pinfunction "DIN_1") (pintype "passive"))
    )
    (net (code "60") (name "Net-(LED55-DOUT)") (class "Default")
      (node (ref "LED55") (pin "3") (pinfunction "DOUT_3") (pintype "passive"))
      (node (ref "LED56") (pin "1") (pinfunction "DIN_1") (pintype "passive"))
    )
    (net (code "61") (name "Net-(LED56-DOUT)") (class "Default")
      (node (ref "LED56") (pin "3") (pinfunction "DOUT_3") (pintype "passive"))
      (node (ref "LED57") (pin "1") (pinfunction "DIN_1") (pintype "passive"))
    )
    (net (code "62") (name "Net-(LED57-DOUT)") (class "Default")
      (node (ref "LED57") (pin "3") (pinfunction "DOUT_3") (pintype "passive"))
      (node (ref "LED58") (pin "1") (pinfunction "DIN_1") (pintype "passive"))
    )
    (net (code "63") (name "Net-(LED58-DOUT)") (class "Default")
      (node (ref "LED58") (pin "3") (pinfunction "DOUT_3") (pintype "passive"))
      (node (ref "LED59") (pin "1") (pinfunction "DIN_1") (pintype "passive"))
    )
    (net (code "64") (name "Net-(LED59-DOUT)") (class "Default")
      (node (ref "LED59") (pin "3") (pinfunction "DOUT_3") (pintype "passive"))
      (node (ref "LED60") (pin "1") (pinfunction "DIN_1") (pintype "passive"))
    )
    (net (code "65") (name "Net-(LED60-DOUT)") (class "Default")
      (node (ref "LED60") (pin "3") (pinfunction "DOUT_3") (pintype "passive"))
      (node (ref "LED61") (pin "1") (pinfunction "DIN_1") (pintype "passive"))
    )
    (net (code "66") (name "Net-(LED61-DOUT)") (class "Default")
      (node (ref "LED61") (pin "3") (pinfunction "DOUT_3") (pintype "passive"))
      (node (ref "LED62") (pin "1") (pinfunction "DIN_1") (pintype "passive"))
    )
    (net (code "67") (name "Net-(LED62-DOUT)") (class "Default")
      (node (ref "LED62") (pin "3") (pinfunction "DOUT_3") (pintype "passive"))
      (node (ref "LED63") (pin "1") (pinfunction "DIN_1") (pintype "passive"))
    )
    (net (code "68") (name "Net-(LED63-DOUT)") (class "Default")
      (node (ref "LED63") (pin "3") (pinfunction "DOUT_3") (pintype "passive"))
      (node (ref "LED64") (pin "1") (pinfunction "DIN_1") (pintype "passive"))
    )
    (net (code "69") (name "Net-(LED64-DOUT)") (class "Default")
      (node (ref "LED64") (pin "3") (pinfunction "DOUT_3") (pintype "passive"))
      (node (ref "LED65") (pin "1") (pinfunction "DIN_1") (pintype "passive"))
    )
    (net (code "70") (name "Net-(LED65-DOUT)") (class "Default")
      (node (ref "LED65") (pin "3") (pinfunction "DOUT_3") (pintype "passive"))
      (node (ref "LED66") (pin "1") (pinfunction "DIN_1") (pintype "passive"))
    )
    (net (code "71") (name "Net-(LED66-DOUT)") (class "Default")
      (node (ref "LED66") (pin "3") (pinfunction "DOUT_3") (pintype "passive"))
      (node (ref "LED67") (pin "1") (pinfunction "DIN_1") (pintype "passive"))
    )
    (net (code "72") (name "Net-(LED67-DOUT)") (class "Default")
      (node (ref "LED67") (pin "3") (pinfunction "DOUT_3") (pintype "passive"))
      (node (ref "LED68") (pin "1") (pinfunction "DIN_1") (pintype "passive"))
    )
    (net (code "73") (name "Net-(LED68-DOUT)") (class "Default")
      (node (ref "LED68") (pin "3") (pinfunction "DOUT_3") (pintype "passive"))
      (node (ref "LED69") (pin "1") (pinfunction "DIN_1") (pintype "passive"))
    )
    (net (code "74") (name "Net-(LED69-DOUT)") (class "Default")
      (node (ref "LED69") (pin "3") (pinfunction "DOUT_3") (pintype "passive"))
      (node (ref "LED70") (pin "1") (pinfunction "DIN_1") (pintype "passive"))
    )
    (net (code "75") (name "Net-(LED70-DOUT)") (class "Default")
      (node (ref "LED70") (pin "3") (pinfunction "DOUT_3") (pintype "passive"))
      (node (ref "LED71") (pin "1") (pinfunction "DIN_1") (pintype "passive"))
    )
    (net (code "76") (name "Net-(LED71-DOUT)") (class "Default")
      (node (ref "LED71") (pin "3") (pinfunction "DOUT_3") (pintype "passive"))
      (node (ref "LED72") (pin "1") (pinfunction "DIN_1") (pintype "passive"))
    )
    (net (code "77") (name "Net-(LED72-DOUT)") (class "Default")
      (node (ref "LED72") (pin "3") (pinfunction "DOUT_3") (pintype "passive"))
      (node (ref "LED73") (pin "1") (pinfunction "DIN_1") (pintype "passive"))
    )
    (net (code "78") (name "Net-(LED73-DOUT)") (class "Default")
      (node (ref "LED73") (pin "3") (pinfunction "DOUT_3") (pintype "passive"))
      (node (ref "LED74") (pin "1") (pinfunction "DIN_1") (pintype "passive"))
    )
    (net (code "79") (name "Net-(LED74-DOUT)") (class "Default")
      (node (ref "LED74") (pin "3") (pinfunction "DOUT_3") (pintype "passive"))
      (node (ref "LED75") (pin "1") (pinfunction "DIN_1") (pintype "passive"))
    )
    (net (code "80") (name "Net-(LED75-DOUT)") (class "Default")
      (node (ref "LED75") (pin "3") (pinfunction "DOUT_3") (pintype "passive"))
      (node (ref "LED76") (pin "1") (pinfunction "DIN_1") (pintype "passive"))
    )
    (net (code "81") (name "Net-(LED76-DOUT)") (class "Default")
      (node (ref "LED76") (pin "3") (pinfunction "DOUT_3") (pintype "passive"))
      (node (ref "LED77") (pin "1") (pinfunction "DIN_1") (pintype "passive"))
    )
    (net (code "82") (name "Net-(LED77-DOUT)") (class "Default")
      (node (ref "LED77") (pin "3") (pinfunction "DOUT_3") (pintype "passive"))
      (node (ref "LED78") (pin "1") (pinfunction "DIN_1") (pintype "passive"))
    )
    (net (code "83") (name "Net-(P2-Pad1)") (class "Default")
      (node (ref "P2") (pin "1") (pinfunction "1_1") (pintype "passive"))
      (node (ref "R3") (pin "1") (pinfunction "1_1") (pintype "passive"))
    )
    (net (code "84") (name "Net-(P3-Pad2)") (class "Default")
      (node (ref "P3") (pin "2") (pinfunction "2_2") (pintype "passive"))
      (node (ref "R4") (pin "1") (pinfunction "1_1") (pintype "passive"))
    )
    (net (code "85") (name "Net-(P4-Pad2)") (class "Default")
      (node (ref "P4") (pin "2") (pinfunction "2_2") (pintype "passive"))
      (node (ref "R7") (pin "2") (pinfunction "2_2") (pintype "passive"))
    )
    (net (code "86") (name "Net-(P5-Pad2)") (class "Default")
      (node (ref "P5") (pin "2") (pinfunction "2_2") (pintype "passive"))
      (node (ref "R8") (pin "2") (pinfunction "2_2") (pintype "passive"))
    )
    (net (code "87") (name "Net-(U1-BOOT)") (class "Default")
      (node (ref "C2") (pin "1") (pinfunction "1_1") (pintype "passive"))
      (node (ref "U1") (pin "6") (pinfunction "BOOT_6") (pintype "passive"))
    )
    (net (code "88") (name "Net-(U1-FB)") (class "Default")
      (node (ref "C3") (pin "1") (pinfunction "1_1") (pintype "passive"))
      (node (ref "R1") (pin "1") (pinfunction "1_1") (pintype "passive"))
      (node (ref "R2") (pin "2") (pinfunction "2_2") (pintype "passive"))
      (node (ref "U1") (pin "4") (pinfunction "FB_4") (pintype "passive"))
    )
    (net (code "89") (name "Net-(U1-SW)") (class "Default")
      (node (ref "C2") (pin "2") (pinfunction "2_2") (pintype "passive"))
      (node (ref "L1") (pin "1") (pinfunction "1_1") (pintype "passive"))
      (node (ref "U1") (pin "2") (pinfunction "SW_2") (pintype "passive"))
    )
    (net (code "90") (name "Net-(U1-VIN)") (class "Default")
      (node (ref "C1") (pin "2") (pinfunction "2_2") (pintype "passive"))
      (node (ref "C86") (pin "1") (pinfunction "1_1") (pintype "passive"))
      (node (ref "R15") (pin "2") (pinfunction "2_2") (pintype "passive"))
      (node (ref "U1") (pin "3") (pinfunction "VIN_3") (pintype "passive"))
    )
    (net (code "91") (name "Net-(U2-GP2)") (class "Default")
      (node (ref "C47") (pin "2") (pinfunction "2_2") (pintype "passive"))
      (node (ref "R7") (pin "1") (pinfunction "1_1") (pintype "passive"))
      (node (ref "R9") (pin "2") (pinfunction "2_2") (pintype "passive"))
      (node (ref "U2") (pin "3") (pinfunction "GP2_3") (pintype "passive"))
    )
    (net (code "92") (name "Net-(U2-GP3)") (class "Default")
      (node (ref "C48") (pin "2") (pinfunction "2_2") (pintype "passive"))
      (node (ref "R10") (pin "2") (pinfunction "2_2") (pintype "passive"))
      (node (ref "R8") (pin "1") (pinfunction "1_1") (pintype "passive"))
      (node (ref "U2") (pin "4") (pinfunction "GP3_4") (pintype "passive"))
    )
    (net (code "93") (name "Net-(U2-GP8)") (class "Default")
      (node (ref "SW1") (pin "1") (pinfunction "1_1") (pintype "passive"))
      (node (ref "SW1") (pin "2") (pinfunction "2_2") (pintype "passive"))
      (node (ref "U2") (pin "9") (pinfunction "GP8_9") (pintype "passive"))
    )
    (net (code "94") (name "Net-(U2-GP27)") (class "Default")
      (node (ref "C7") (pin "2") (pinfunction "2_2") (pintype "passive"))
      (node (ref "R13") (pin "1") (pinfunction "1_1") (pintype "passive"))
      (node (ref "R14") (pin "2") (pinfunction "2_2") (pintype "passive"))
      (node (ref "R6") (pin "2") (pinfunction "2_2") (pintype "passive"))
      (node (ref "U2") (pin "18") (pinfunction "GP27_18") (pintype "passive"))
    )
    (net (code "95") (name "Net-(U2-GP28)") (class "Default")
      (node (ref "C8") (pin "2") (pinfunction "2_2") (pintype "passive"))
      (node (ref "R11") (pin "1") (pinfunction "1_1") (pintype "passive"))
      (node (ref "R12") (pin "2") (pinfunction "2_2") (pintype "passive"))
      (node (ref "R5") (pin "2") (pinfunction "2_2") (pintype "passive"))
      (node (ref "U2") (pin "19") (pinfunction "GP28_19") (pintype "passive"))
    )
    (net (code "96") (name "unconnected-(LED36-DOUT-Pad3)") (class "Default")
      (node (ref "LED36") (pin "3") (pinfunction "DOUT_3") (pintype "passive+no_connect"))
    )
    (net (code "97") (name "unconnected-(LED78-DOUT-Pad3)") (class "Default")
      (node (ref "LED78") (pin "3") (pinfunction "DOUT_3") (pintype "passive+no_connect"))
    )
    (net (code "98") (name "unconnected-(U1-EN-Pad5)") (class "Default")
      (node (ref "U1") (pin "5") (pinfunction "EN_5") (pintype "passive+no_connect"))
    )
    (net (code "99") (name "unconnected-(U2-GP0-Pad1)") (class "Default")
      (node (ref "U2") (pin "1") (pinfunction "GP0_1") (pintype "passive+no_connect"))
    )
    (net (code "100") (name "unconnected-(U2-GP1-Pad2)") (class "Default")
      (node (ref "U2") (pin "2") (pinfunction "GP1_2") (pintype "passive+no_connect"))
    )
    (net (code "101") (name "unconnected-(U2-GP4-Pad5)") (class "Default")
      (node (ref "U2") (pin "5") (pinfunction "GP4_5") (pintype "passive+no_connect"))
    )
    (net (code "102") (name "unconnected-(U2-GP5-Pad6)") (class "Default")
      (node (ref "U2") (pin "6") (pinfunction "GP5_6") (pintype "passive+no_connect"))
    )
    (net (code "103") (name "unconnected-(U2-GP6-Pad7)") (class "Default")
      (node (ref "U2") (pin "7") (pinfunction "GP6_7") (pintype "passive+no_connect"))
    )
    (net (code "104") (name "unconnected-(U2-GP7-Pad8)") (class "Default")
      (node (ref "U2") (pin "8") (pinfunction "GP7_8") (pintype "passive+no_connect"))
    )
    (net (code "105") (name "unconnected-(U2-GP9-Pad10)") (class "Default")
      (node (ref "U2") (pin "10") (pinfunction "GP9_10") (pintype "passive+no_connect"))
    )
    (net (code "106") (name "unconnected-(U2-GP10-Pad11)") (class "Default")
      (node (ref "U2") (pin "11") (pinfunction "GP10_11") (pintype "passive+no_connect"))
    )
    (net (code "107") (name "unconnected-(U2-GP11-Pad12)") (class "Default")
      (node (ref "U2") (pin "12") (pinfunction "GP11_12") (pintype "passive+no_connect"))
    )
    (net (code "108") (name "unconnected-(U2-GP12-Pad13)") (class "Default")
      (node (ref "U2") (pin "13") (pinfunction "GP12_13") (pintype "passive+no_connect"))
    )
    (net (code "109") (name "unconnected-(U2-GP13-Pad14)") (class "Default")
      (node (ref "U2") (pin "14") (pinfunction "GP13_14") (pintype "passive+no_connect"))
    )
    (net (code "110") (name "unconnected-(U2-GP26-Pad17)") (class "Default")
      (node (ref "U2") (pin "17") (pinfunction "GP26_17") (pintype "passive+no_connect"))
    )
    (net (code "111") (name "unconnected-(U2-GP29-Pad20)") (class "Default")
      (node (ref "U2") (pin "20") (pinfunction "GP29_20") (pintype "passive+no_connect"))
    )
  )
)
